# tf1230.net
KiCad netlist of a schematic drawn in EAGLE
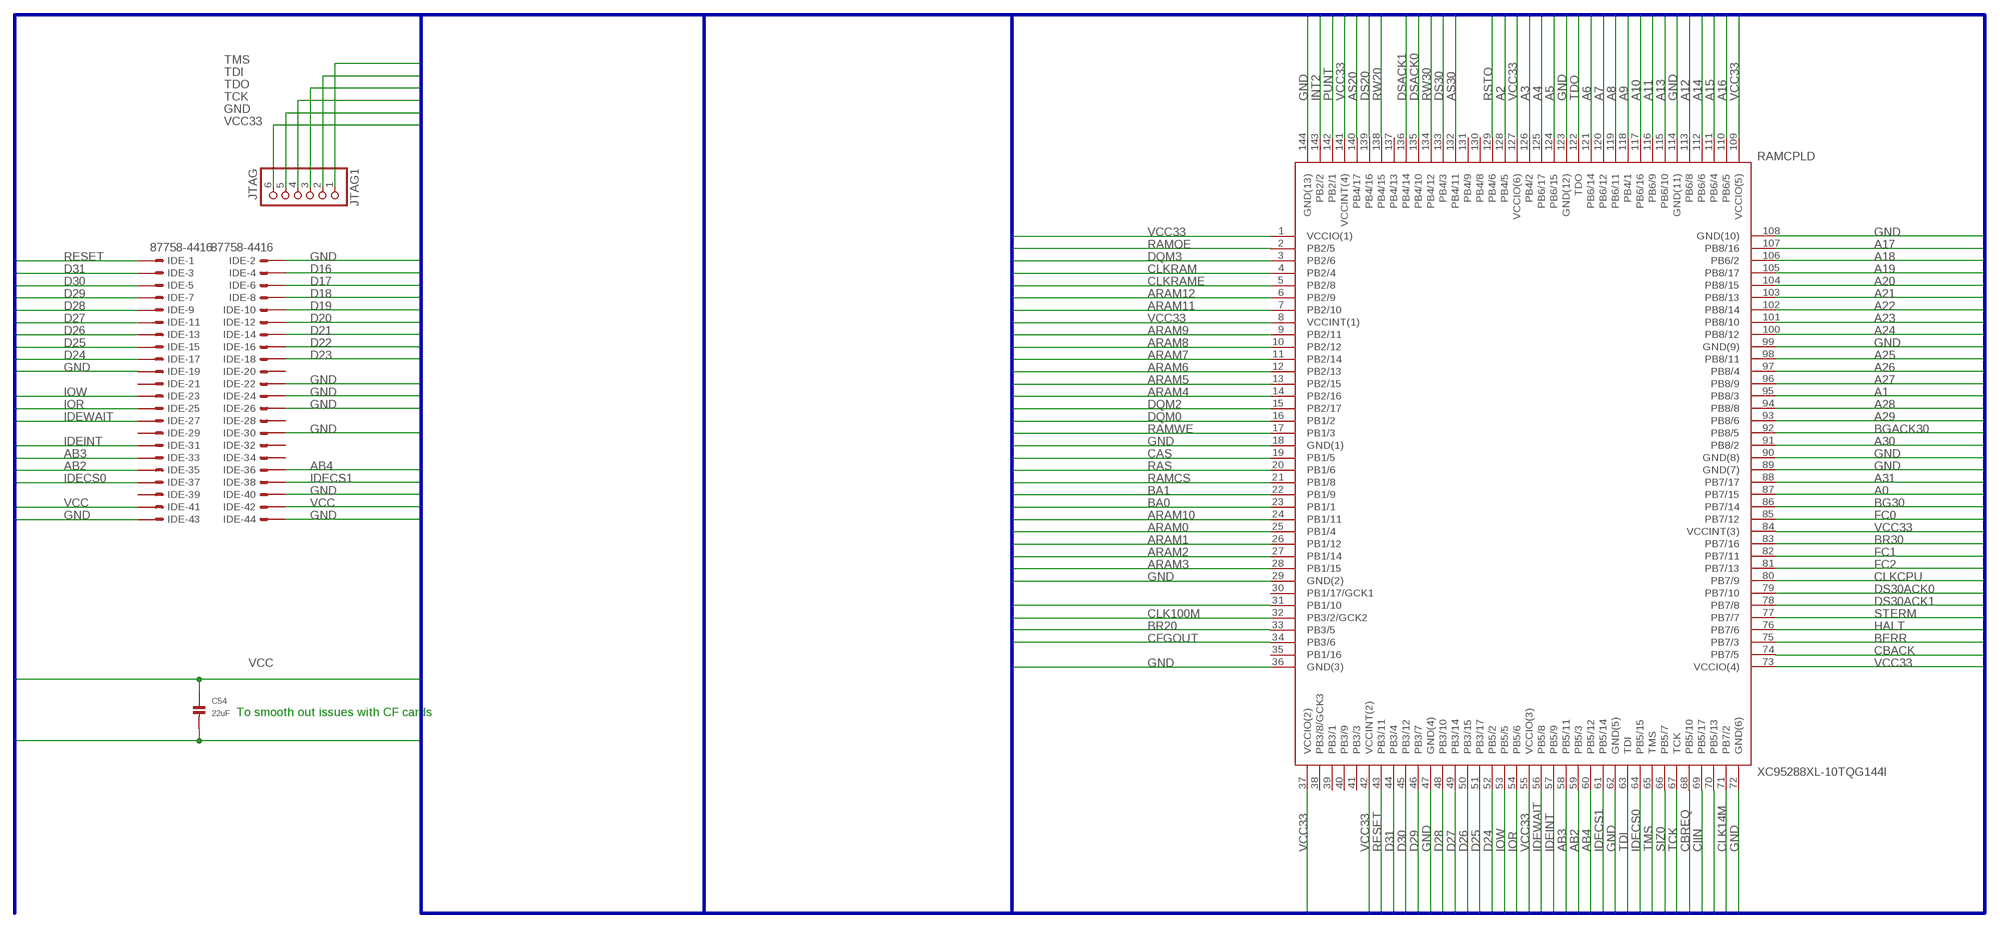
[diagram p0: schematic, sheet 1]
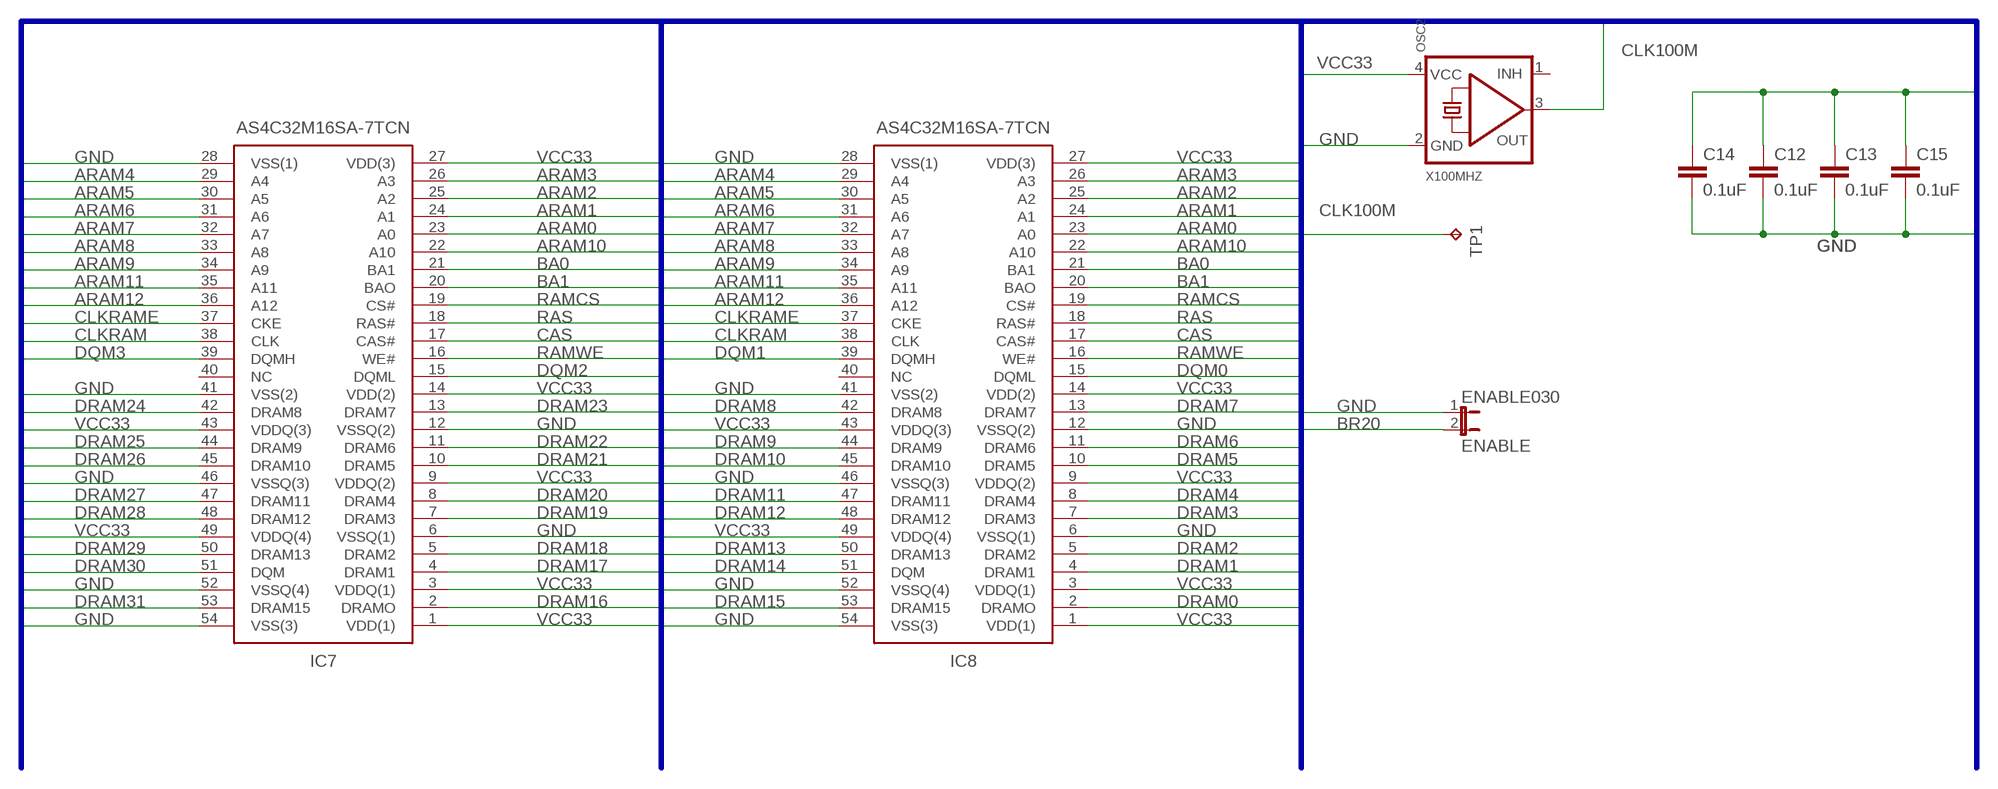
[diagram p1: schematic, sheet 2]
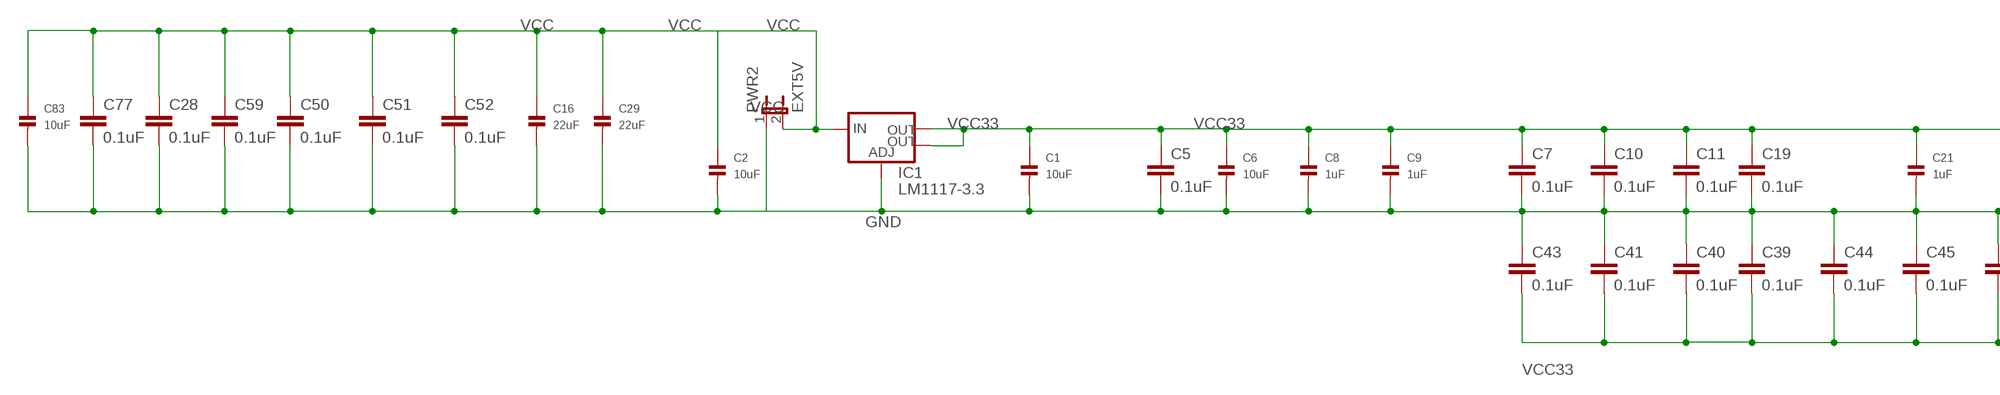
[diagram p2: schematic, sheet 3, part 1 of 2]
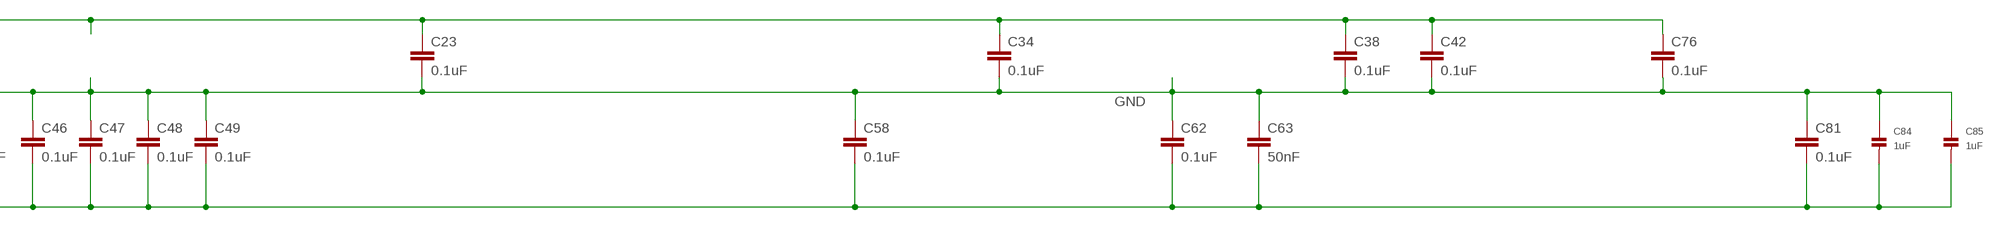
[diagram p3: schematic, sheet 3, part 2 of 2]
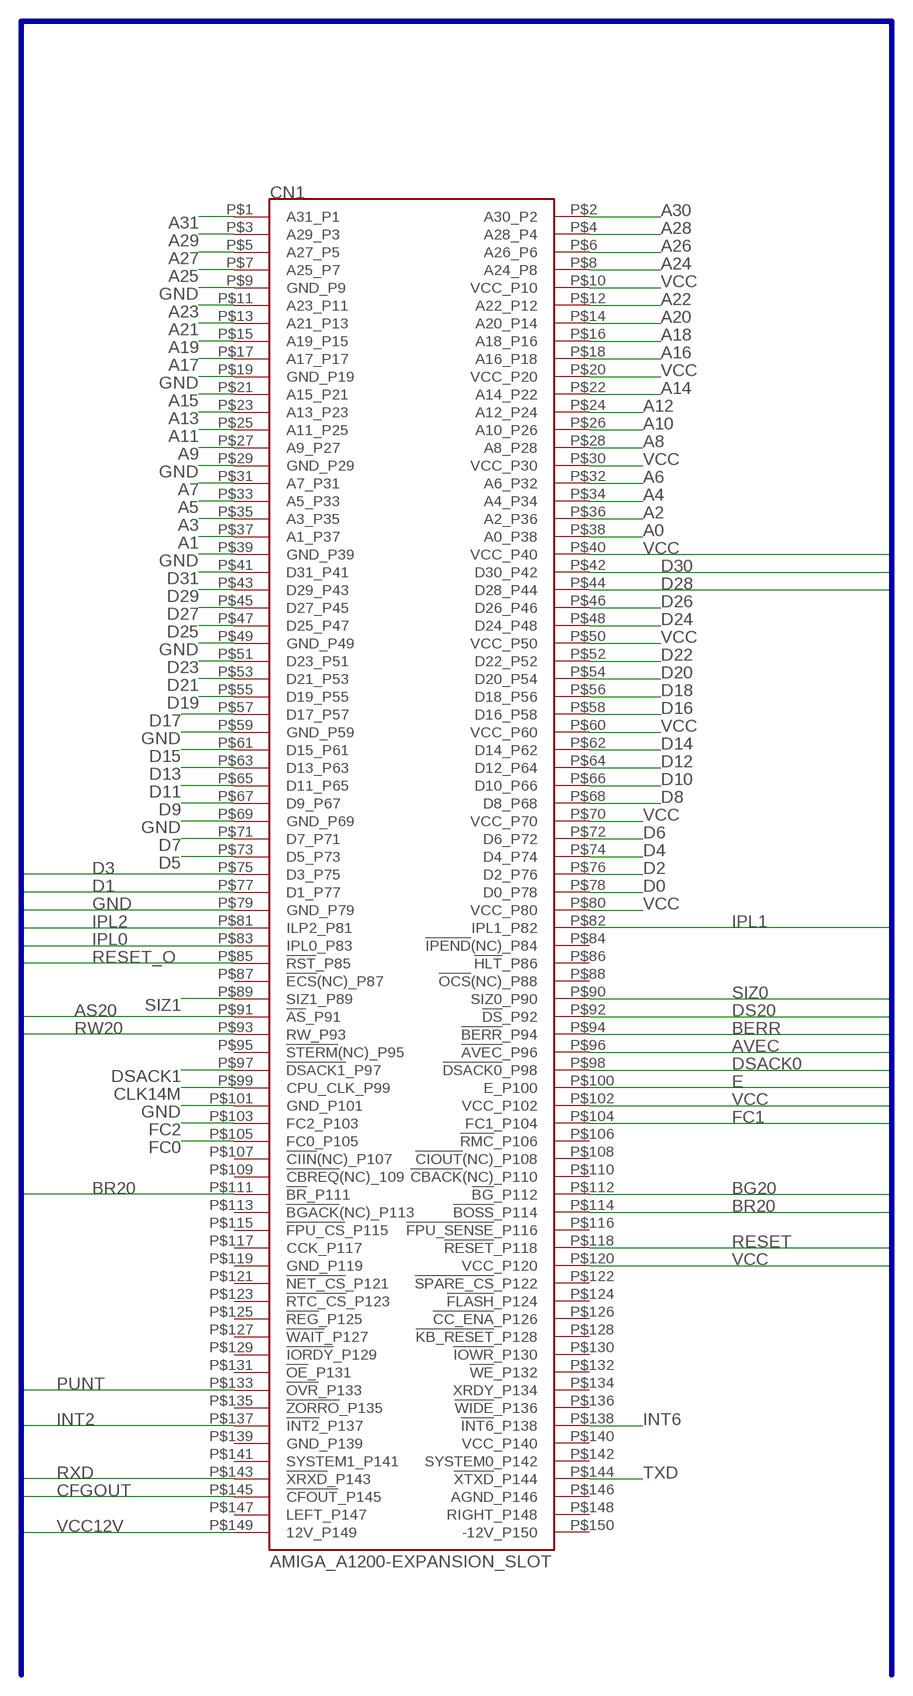
[diagram p4: schematic, sheet 4]
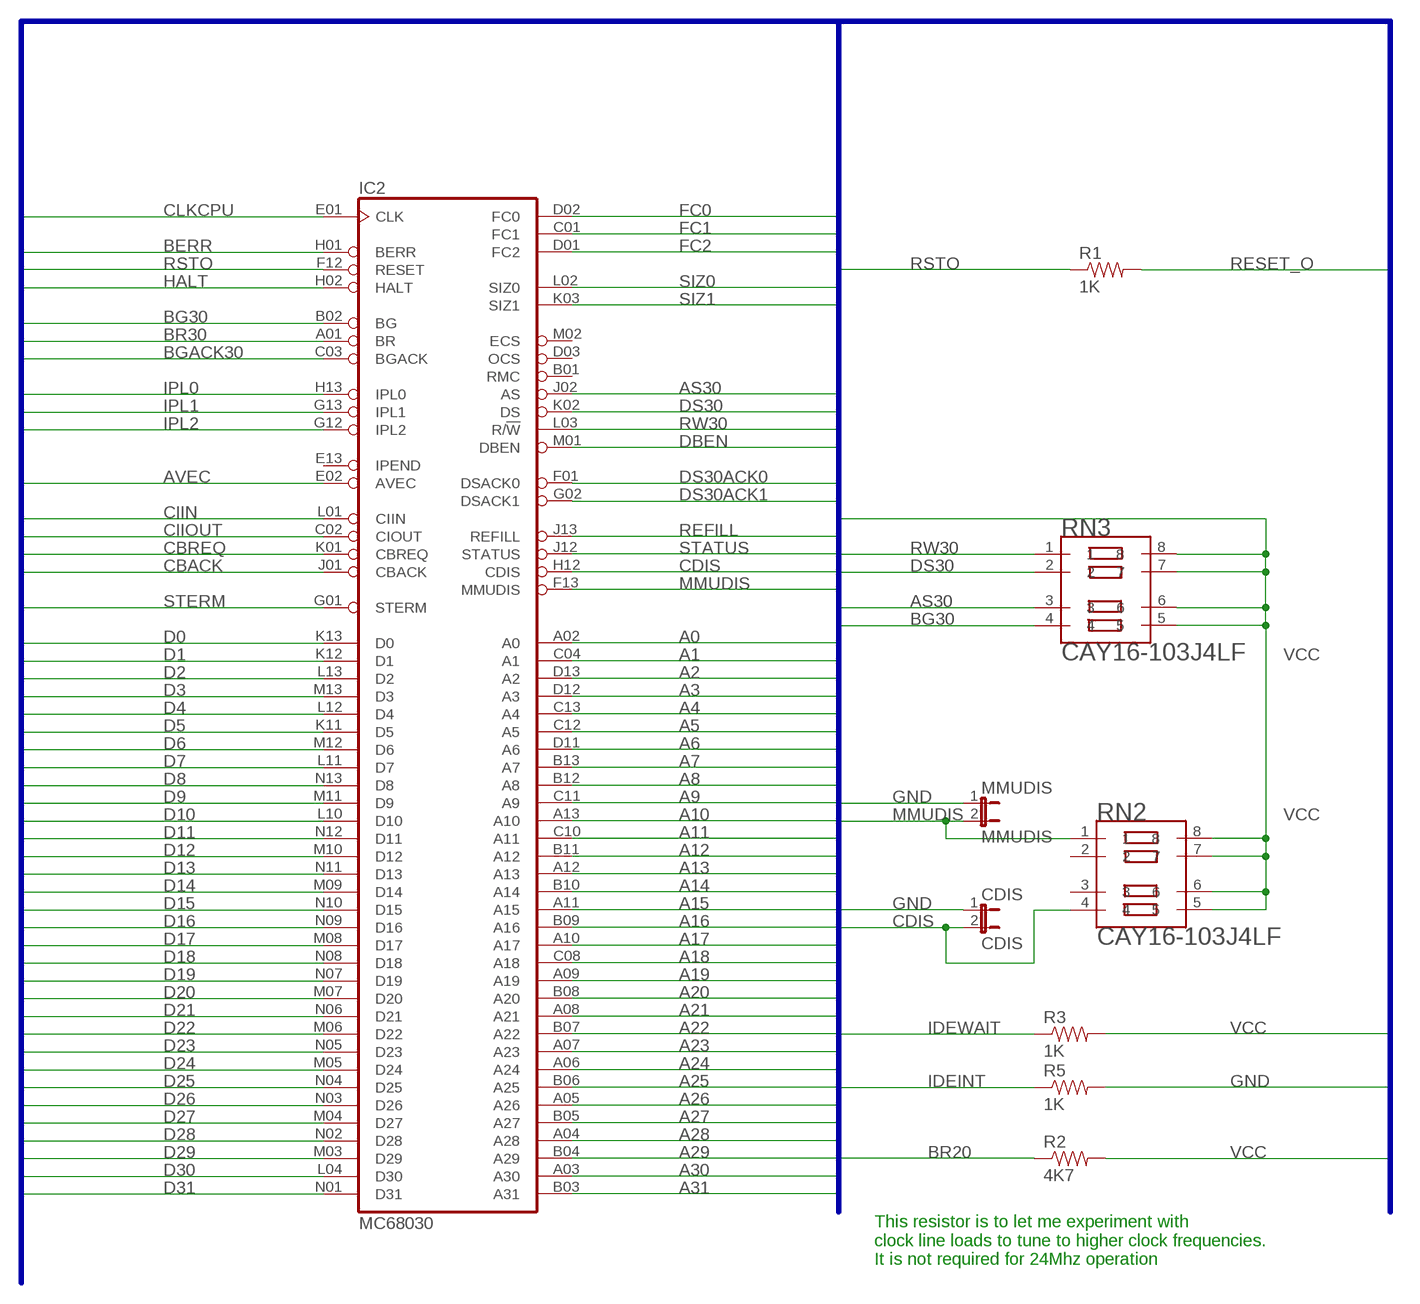
[diagram p5: schematic, sheet 5]
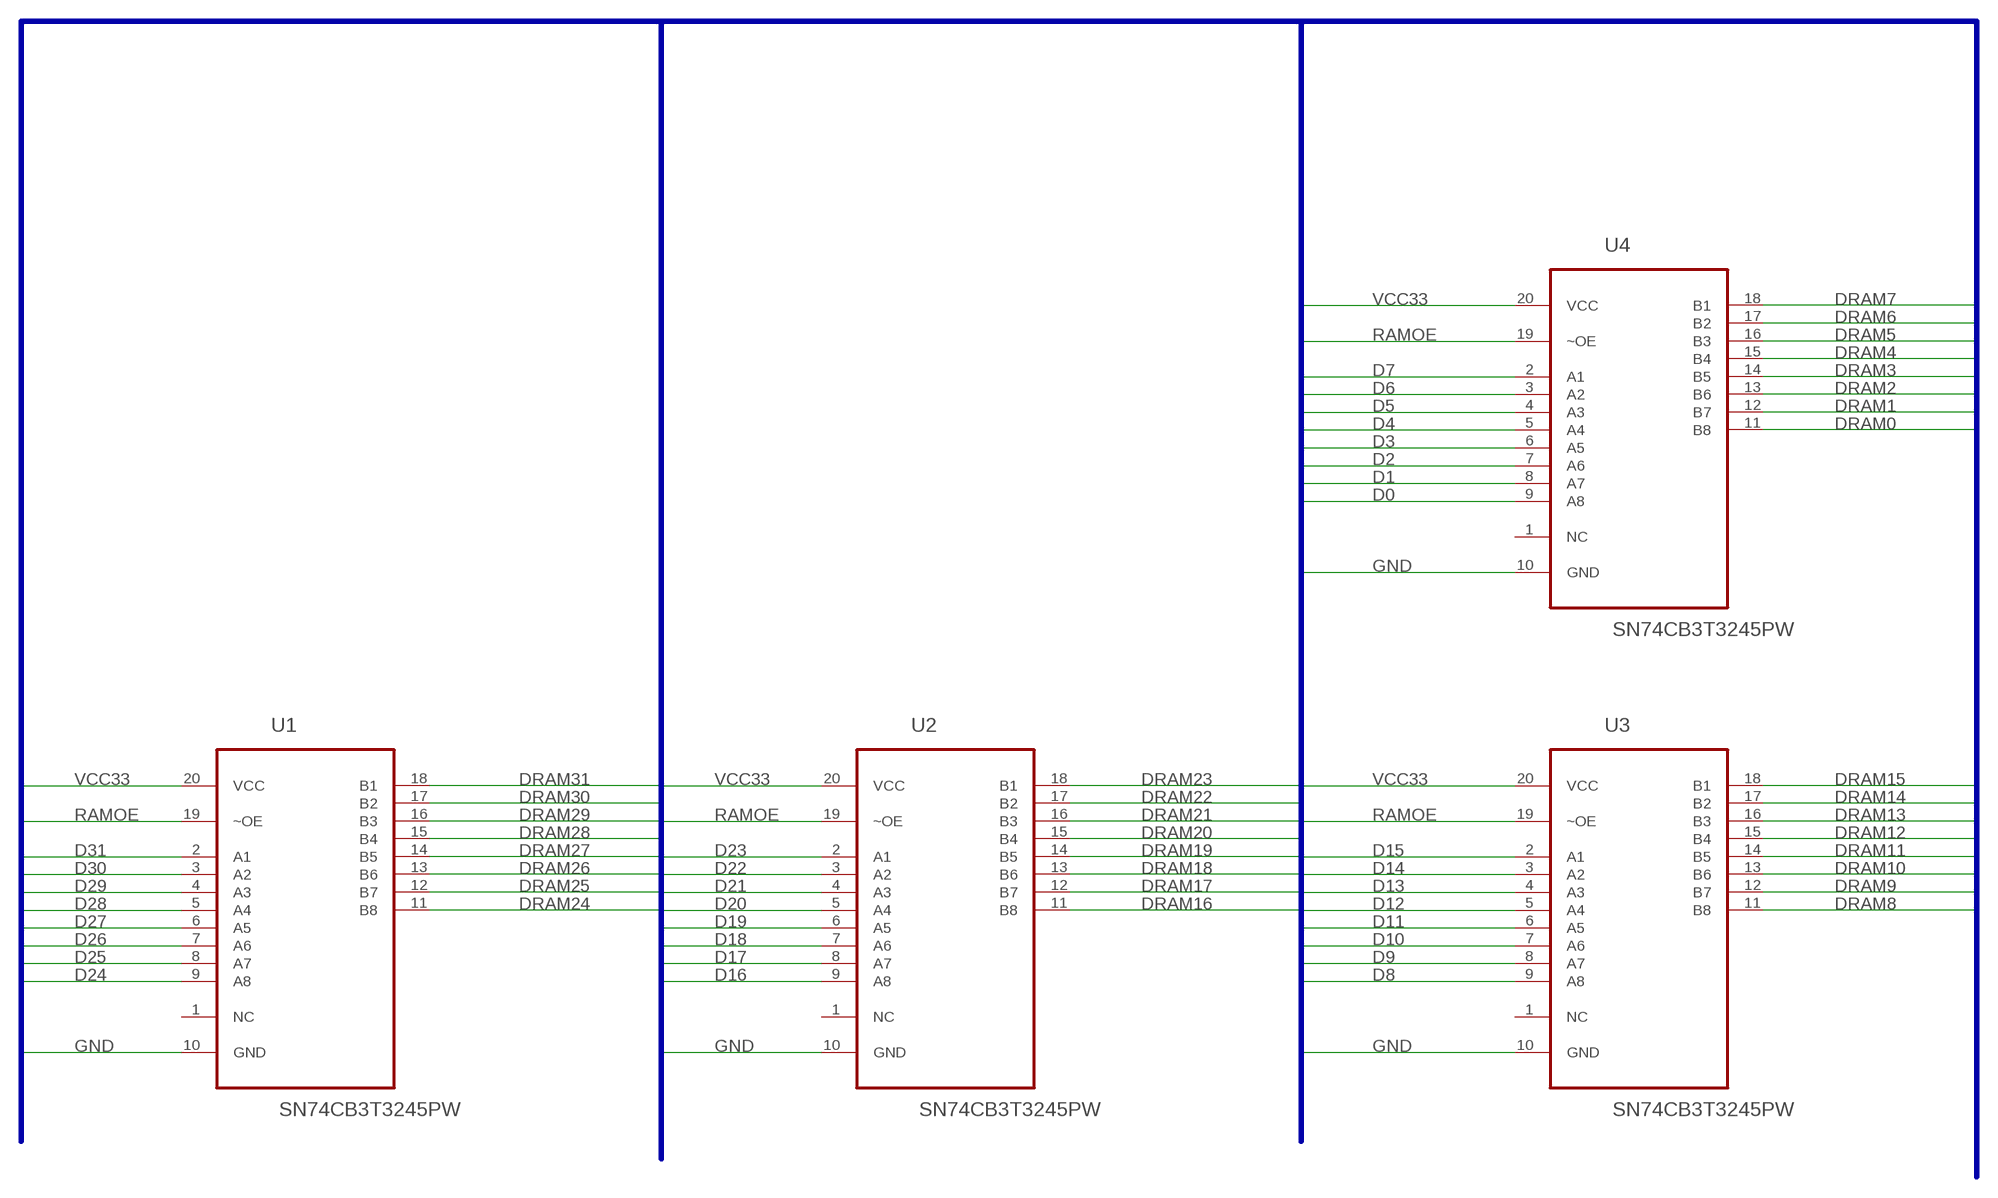
[diagram p6: schematic, sheet 6]

(export (version "E")
  (design (tool "Eeschema 10.0.6"))
  (components
    (comp (ref "CDIS")
      (value "CDIS")
      (footprint "eagle-import:1X02")
      (libsource (lib "eagle-import") (part "JUMPER-2PTH"))
    )
    (comp (ref "IC2")
      (value "MC68030")
      (footprint "eagle-import:MPGA128")
      (fields (field (name "MF") "MOTOROLA") (field (name "MPN") "MC68030RC50C"))
      (libsource (lib "eagle-import") (part "MC68030RC"))
    )
    (comp (ref "MMUDIS")
      (value "MMUDIS")
      (footprint "eagle-import:1X02")
      (libsource (lib "eagle-import") (part "JUMPER-2PTH"))
    )
    (comp (ref "R1")
      (value "1K")
      (footprint "eagle-import:0603")
      (libsource (lib "eagle-import") (part "0.05OHM-1/5W-1%(0603)"))
    )
    (comp (ref "R2")
      (value "4K7")
      (footprint "eagle-import:0603")
      (libsource (lib "eagle-import") (part "0.05OHM-1/5W-1%(0603)"))
    )
    (comp (ref "R3")
      (value "1K")
      (footprint "eagle-import:0603")
      (libsource (lib "eagle-import") (part "0.05OHM-1/5W-1%(0603)"))
    )
    (comp (ref "R5")
      (value "1K")
      (footprint "eagle-import:0603")
      (libsource (lib "eagle-import") (part "0.05OHM-1/5W-1%(0603)"))
    )
    (comp (ref "RN2")
      (value "CAY16-103J4LF")
      (footprint "eagle-import:RESCAXE80P320X160-8N")
      (fields (field (name "MF") "Bourns"))
      (libsource (lib "eagle-import") (part "CAY16-103J4LF"))
    )
    (comp (ref "RN3")
      (value "CAY16-103J4LF")
      (footprint "eagle-import:RESCAXE80P320X160-8N")
      (fields (field (name "MF") "Bourns"))
      (libsource (lib "eagle-import") (part "CAY16-103J4LF"))
    )
    (comp (ref "U1")
      (value "SN74CB3T3245PW")
      (footprint "eagle-import:SOP65P640X120-20N")
      (fields (field (name "MF") "Texas Instruments"))
      (libsource (lib "eagle-import") (part "SN74CB3T3245PW"))
    )
    (comp (ref "U2")
      (value "SN74CB3T3245PW")
      (footprint "eagle-import:SOP65P640X120-20N")
      (fields (field (name "MF") "Texas Instruments"))
      (libsource (lib "eagle-import") (part "SN74CB3T3245PW"))
    )
    (comp (ref "U3")
      (value "SN74CB3T3245PW")
      (footprint "eagle-import:SOP65P640X120-20N")
      (fields (field (name "MF") "Texas Instruments"))
      (libsource (lib "eagle-import") (part "SN74CB3T3245PW"))
    )
    (comp (ref "U4")
      (value "SN74CB3T3245PW")
      (footprint "eagle-import:SOP65P640X120-20N")
      (fields (field (name "MF") "Texas Instruments"))
      (libsource (lib "eagle-import") (part "SN74CB3T3245PW"))
    )
    (comp (ref "C54")
      (value "22uF")
      (footprint "eagle-import:1206")
      (libsource (lib "eagle-import") (part "CAP_CERAMIC1206"))
    )
    (comp (ref "IDE")
      (value "87758-4416")
      (footprint "eagle-import:87758-4416")
      (fields (field (name "MF") "MOLEX"))
      (libsource (lib "eagle-import") (part "87758-4416"))
    )
    (comp (ref "JTAG1")
      (value "JTAG")
      (footprint "eagle-import:1X06_ROUND")
      (libsource (lib "eagle-import") (part "HEADER-1X6ROUND"))
    )
    (comp (ref "RAMCPLD")
      (value "XC95288XL-10TQG144I")
      (footprint "eagle-import:SAMACSYS_PARTS_QFP50P2200X2200X160-144N")
      (fields
        (field (name "MANUFACTURER_PART_NUMBER") "XC95144XL-10TQG144I")
        (field (name "RS_PART_NUMBER") "6260624")
      )
      (libsource (lib "eagle-import") (part "SAMACSYS_PARTS_XC95144XL-10TQG144I"))
    )
    (comp (ref "C12")
      (value "0.1uF")
      (footprint "eagle-import:0603-CAP")
      (libsource (lib "eagle-import") (part "0.1UF-25V(+80/-20%)(0603)"))
    )
    (comp (ref "C13")
      (value "0.1uF")
      (footprint "eagle-import:0603-CAP")
      (libsource (lib "eagle-import") (part "0.1UF-25V(+80/-20%)(0603)"))
    )
    (comp (ref "C14")
      (value "0.1uF")
      (footprint "eagle-import:0603-CAP")
      (libsource (lib "eagle-import") (part "0.1UF-25V(+80/-20%)(0603)"))
    )
    (comp (ref "C15")
      (value "0.1uF")
      (footprint "eagle-import:0603-CAP")
      (libsource (lib "eagle-import") (part "0.1UF-25V(+80/-20%)(0603)"))
    )
    (comp (ref "ENABLE030")
      (value "ENABLE")
      (footprint "eagle-import:1X02")
      (libsource (lib "eagle-import") (part "JUMPER-2PTH"))
    )
    (comp (ref "IC7")
      (value "AS4C32M16SA-7TCN")
      (footprint "eagle-import:SOP80P1176X120-54N")
      (fields
        (field (name "MANUFACTURER_PART_NUMBER") "MT48LC16M16A2P-6A:G")
        (field (name "RS_PART_NUMBER") "7824553")
      )
      (libsource (lib "eagle-import") (part "MT48LC16M16A2P-6A_G"))
    )
    (comp (ref "IC8")
      (value "AS4C32M16SA-7TCN")
      (footprint "eagle-import:SOP80P1176X120-54N")
      (fields
        (field (name "MANUFACTURER_PART_NUMBER") "MT48LC16M16A2P-6A:G")
        (field (name "RS_PART_NUMBER") "7824553")
      )
      (libsource (lib "eagle-import") (part "MT48LC16M16A2P-6A_G"))
    )
    (comp (ref "OSC2")
      (value "X100MHZ")
      (footprint "eagle-import:OSC_7X5MM")
      (libsource (lib "eagle-import") (part "OSCILLATOR"))
    )
    (comp (ref "TP1")
      (value "TPB1,27")
      (footprint "eagle-import:B1,27")
      (libsource (lib "eagle-import") (part "TPB1,27"))
    )
    (comp (ref "CN1")
      (value "AMIGA_A1200-EXPANSION_SLOT")
      (footprint "eagle-import:AMIGA_CON_150")
      (libsource (lib "eagle-import") (part "AMIGA_A1200-EXPANSION_SLOT"))
    )
    (comp (ref "C1")
      (value "10uF")
      (footprint "eagle-import:1206")
      (libsource (lib "eagle-import") (part "CAP_CERAMIC1206"))
    )
    (comp (ref "C2")
      (value "10uF")
      (footprint "eagle-import:1206")
      (libsource (lib "eagle-import") (part "CAP_CERAMIC1206"))
    )
    (comp (ref "C5")
      (value "0.1uF")
      (footprint "eagle-import:0603-CAP")
      (libsource (lib "eagle-import") (part "0.1UF-25V(+80/-20%)(0603)"))
    )
    (comp (ref "C6")
      (value "10uF")
      (footprint "eagle-import:1206")
      (libsource (lib "eagle-import") (part "CAP_CERAMIC1206"))
    )
    (comp (ref "C7")
      (value "0.1uF")
      (footprint "eagle-import:0603-CAP")
      (libsource (lib "eagle-import") (part "0.1UF-25V(+80/-20%)(0603)"))
    )
    (comp (ref "C8")
      (value "1uF")
      (footprint "eagle-import:1206")
      (libsource (lib "eagle-import") (part "CAP_CERAMIC1206"))
    )
    (comp (ref "C9")
      (value "1uF")
      (footprint "eagle-import:1206")
      (libsource (lib "eagle-import") (part "CAP_CERAMIC1206"))
    )
    (comp (ref "C10")
      (value "0.1uF")
      (footprint "eagle-import:0603-CAP")
      (libsource (lib "eagle-import") (part "0.1UF-25V(+80/-20%)(0603)"))
    )
    (comp (ref "C11")
      (value "0.1uF")
      (footprint "eagle-import:0603-CAP")
      (libsource (lib "eagle-import") (part "0.1UF-25V(+80/-20%)(0603)"))
    )
    (comp (ref "C16")
      (value "22uF")
      (footprint "eagle-import:1206")
      (libsource (lib "eagle-import") (part "CAP_CERAMIC1206"))
    )
    (comp (ref "C19")
      (value "0.1uF")
      (footprint "eagle-import:0603-CAP")
      (libsource (lib "eagle-import") (part "0.1UF-25V(+80/-20%)(0603)"))
    )
    (comp (ref "C21")
      (value "1uF")
      (footprint "eagle-import:1206")
      (libsource (lib "eagle-import") (part "CAP_CERAMIC1206"))
    )
    (comp (ref "C23")
      (value "0.1uF")
      (footprint "eagle-import:0603-CAP")
      (libsource (lib "eagle-import") (part "0.1UF-25V(+80/-20%)(0603)"))
    )
    (comp (ref "C28")
      (value "0.1uF")
      (footprint "eagle-import:0603-CAP")
      (libsource (lib "eagle-import") (part "0.1UF-25V(+80/-20%)(0603)"))
    )
    (comp (ref "C29")
      (value "22uF")
      (footprint "eagle-import:1206")
      (libsource (lib "eagle-import") (part "CAP_CERAMIC1206"))
    )
    (comp (ref "C34")
      (value "0.1uF")
      (footprint "eagle-import:0603-CAP")
      (libsource (lib "eagle-import") (part "0.1UF-25V(+80/-20%)(0603)"))
    )
    (comp (ref "C38")
      (value "0.1uF")
      (footprint "eagle-import:0603-CAP")
      (libsource (lib "eagle-import") (part "0.1UF-25V(+80/-20%)(0603)"))
    )
    (comp (ref "C39")
      (value "0.1uF")
      (footprint "eagle-import:0603-CAP")
      (libsource (lib "eagle-import") (part "0.1UF-25V(+80/-20%)(0603)"))
    )
    (comp (ref "C40")
      (value "0.1uF")
      (footprint "eagle-import:0603-CAP")
      (libsource (lib "eagle-import") (part "0.1UF-25V(+80/-20%)(0603)"))
    )
    (comp (ref "C41")
      (value "0.1uF")
      (footprint "eagle-import:0603-CAP")
      (libsource (lib "eagle-import") (part "0.1UF-25V(+80/-20%)(0603)"))
    )
    (comp (ref "C42")
      (value "0.1uF")
      (footprint "eagle-import:0603-CAP")
      (libsource (lib "eagle-import") (part "0.1UF-25V(+80/-20%)(0603)"))
    )
    (comp (ref "C43")
      (value "0.1uF")
      (footprint "eagle-import:0603-CAP")
      (libsource (lib "eagle-import") (part "0.1UF-25V(+80/-20%)(0603)"))
    )
    (comp (ref "C44")
      (value "0.1uF")
      (footprint "eagle-import:0603-CAP")
      (libsource (lib "eagle-import") (part "0.1UF-25V(+80/-20%)(0603)"))
    )
    (comp (ref "C45")
      (value "0.1uF")
      (footprint "eagle-import:0603-CAP")
      (libsource (lib "eagle-import") (part "0.1UF-25V(+80/-20%)(0603)"))
    )
    (comp (ref "C46")
      (value "0.1uF")
      (footprint "eagle-import:0603-CAP")
      (libsource (lib "eagle-import") (part "0.1UF-25V(+80/-20%)(0603)"))
    )
    (comp (ref "C47")
      (value "0.1uF")
      (footprint "eagle-import:0603-CAP")
      (libsource (lib "eagle-import") (part "0.1UF-25V(+80/-20%)(0603)"))
    )
    (comp (ref "C48")
      (value "0.1uF")
      (footprint "eagle-import:0603-CAP")
      (libsource (lib "eagle-import") (part "0.1UF-25V(+80/-20%)(0603)"))
    )
    (comp (ref "C49")
      (value "0.1uF")
      (footprint "eagle-import:0603-CAP")
      (libsource (lib "eagle-import") (part "0.1UF-25V(+80/-20%)(0603)"))
    )
    (comp (ref "C50")
      (value "0.1uF")
      (footprint "eagle-import:0603-CAP")
      (libsource (lib "eagle-import") (part "0.1UF-25V(+80/-20%)(0603)"))
    )
    (comp (ref "C51")
      (value "0.1uF")
      (footprint "eagle-import:0603-CAP")
      (libsource (lib "eagle-import") (part "0.1UF-25V(+80/-20%)(0603)"))
    )
    (comp (ref "C52")
      (value "0.1uF")
      (footprint "eagle-import:0603-CAP")
      (libsource (lib "eagle-import") (part "0.1UF-25V(+80/-20%)(0603)"))
    )
    (comp (ref "C58")
      (value "0.1uF")
      (footprint "eagle-import:0603-CAP")
      (libsource (lib "eagle-import") (part "0.1UF-25V(+80/-20%)(0603)"))
    )
    (comp (ref "C59")
      (value "0.1uF")
      (footprint "eagle-import:0603-CAP")
      (libsource (lib "eagle-import") (part "0.1UF-25V(+80/-20%)(0603)"))
    )
    (comp (ref "C62")
      (value "0.1uF")
      (footprint "eagle-import:0603-CAP")
      (libsource (lib "eagle-import") (part "0.1UF-25V(+80/-20%)(0603)"))
    )
    (comp (ref "C63")
      (value "50nF")
      (footprint "eagle-import:0603-CAP")
      (libsource (lib "eagle-import") (part "0.1UF-25V(+80/-20%)(0603)"))
    )
    (comp (ref "C76")
      (value "0.1uF")
      (footprint "eagle-import:0603-CAP")
      (libsource (lib "eagle-import") (part "0.1UF-25V(+80/-20%)(0603)"))
    )
    (comp (ref "C77")
      (value "0.1uF")
      (footprint "eagle-import:0603-CAP")
      (libsource (lib "eagle-import") (part "0.1UF-25V(+80/-20%)(0603)"))
    )
    (comp (ref "C81")
      (value "0.1uF")
      (footprint "eagle-import:0603-CAP")
      (libsource (lib "eagle-import") (part "0.1UF-25V(+80/-20%)(0603)"))
    )
    (comp (ref "C83")
      (value "10uF")
      (footprint "eagle-import:1206")
      (libsource (lib "eagle-import") (part "CAP_CERAMIC1206"))
    )
    (comp (ref "C84")
      (value "1uF")
      (footprint "eagle-import:1206")
      (libsource (lib "eagle-import") (part "CAP_CERAMIC1206"))
    )
    (comp (ref "C85")
      (value "1uF")
      (footprint "eagle-import:1206")
      (libsource (lib "eagle-import") (part "CAP_CERAMIC1206"))
    )
    (comp (ref "IC1")
      (value "LM1117-3.3")
      (footprint "eagle-import:SOT223")
      (libsource (lib "eagle-import") (part "V_REG_LM1117SOT223"))
    )
    (comp (ref "PWR2")
      (value "EXT5V")
      (footprint "eagle-import:1X02")
      (libsource (lib "eagle-import") (part "JUMPER-2PTH"))
    )
  )
  (nets
    (net (code "1") (name "A0") (class "Default")
      (node (ref "CN1") (pin "P$38") (pinfunction "A0_P38_P$38") (pintype "bidirectional"))
      (node (ref "IC2") (pin "A02") (pinfunction "A0_A02") (pintype "output"))
      (node (ref "RAMCPLD") (pin "87") (pinfunction "PB7/15_87") (pintype "input"))
    )
    (net (code "2") (name "A1") (class "Default")
      (node (ref "CN1") (pin "P$37") (pinfunction "A1_P37_P$37") (pintype "bidirectional"))
      (node (ref "IC2") (pin "C04") (pinfunction "A1_C04") (pintype "output"))
      (node (ref "RAMCPLD") (pin "95") (pinfunction "PB8/3_95") (pintype "input"))
    )
    (net (code "3") (name "A2") (class "Default")
      (node (ref "CN1") (pin "P$36") (pinfunction "A2_P36_P$36") (pintype "bidirectional"))
      (node (ref "IC2") (pin "D13") (pinfunction "A2_D13") (pintype "output"))
      (node (ref "RAMCPLD") (pin "128") (pinfunction "PB4/5_128") (pintype "input"))
    )
    (net (code "4") (name "A3") (class "Default")
      (node (ref "CN1") (pin "P$35") (pinfunction "A3_P35_P$35") (pintype "bidirectional"))
      (node (ref "IC2") (pin "D12") (pinfunction "A3_D12") (pintype "output"))
      (node (ref "RAMCPLD") (pin "126") (pinfunction "PB4/2_126") (pintype "input"))
    )
    (net (code "5") (name "A4") (class "Default")
      (node (ref "CN1") (pin "P$34") (pinfunction "A4_P34_P$34") (pintype "bidirectional"))
      (node (ref "IC2") (pin "C13") (pinfunction "A4_C13") (pintype "output"))
      (node (ref "RAMCPLD") (pin "125") (pinfunction "PB6/17_125") (pintype "input"))
    )
    (net (code "6") (name "A5") (class "Default")
      (node (ref "CN1") (pin "P$33") (pinfunction "A5_P33_P$33") (pintype "bidirectional"))
      (node (ref "IC2") (pin "C12") (pinfunction "A5_C12") (pintype "output"))
      (node (ref "RAMCPLD") (pin "124") (pinfunction "PB6/15_124") (pintype "input"))
    )
    (net (code "7") (name "A6") (class "Default")
      (node (ref "CN1") (pin "P$32") (pinfunction "A6_P32_P$32") (pintype "bidirectional"))
      (node (ref "IC2") (pin "D11") (pinfunction "A6_D11") (pintype "output"))
      (node (ref "RAMCPLD") (pin "121") (pinfunction "PB6/14_121") (pintype "input"))
    )
    (net (code "8") (name "A7") (class "Default")
      (node (ref "CN1") (pin "P$31") (pinfunction "A7_P31_P$31") (pintype "bidirectional"))
      (node (ref "IC2") (pin "B13") (pinfunction "A7_B13") (pintype "output"))
      (node (ref "RAMCPLD") (pin "120") (pinfunction "PB6/12_120") (pintype "input"))
    )
    (net (code "9") (name "A8") (class "Default")
      (node (ref "CN1") (pin "P$28") (pinfunction "A8_P28_P$28") (pintype "bidirectional"))
      (node (ref "IC2") (pin "B12") (pinfunction "A8_B12") (pintype "output"))
      (node (ref "RAMCPLD") (pin "119") (pinfunction "PB6/11_119") (pintype "input"))
    )
    (net (code "10") (name "A9") (class "Default")
      (node (ref "CN1") (pin "P$27") (pinfunction "A9_P27_P$27") (pintype "bidirectional"))
      (node (ref "IC2") (pin "C11") (pinfunction "A9_C11") (pintype "output"))
      (node (ref "RAMCPLD") (pin "118") (pinfunction "PB4/1_118") (pintype "input"))
    )
    (net (code "11") (name "A10") (class "Default")
      (node (ref "CN1") (pin "P$26") (pinfunction "A10_P26_P$26") (pintype "bidirectional"))
      (node (ref "IC2") (pin "A13") (pinfunction "A10_A13") (pintype "output"))
      (node (ref "RAMCPLD") (pin "117") (pinfunction "PB6/16_117") (pintype "input"))
    )
    (net (code "12") (name "A11") (class "Default")
      (node (ref "CN1") (pin "P$25") (pinfunction "A11_P25_P$25") (pintype "bidirectional"))
      (node (ref "IC2") (pin "C10") (pinfunction "A11_C10") (pintype "output"))
      (node (ref "RAMCPLD") (pin "116") (pinfunction "PB6/9_116") (pintype "input"))
    )
    (net (code "13") (name "A12") (class "Default")
      (node (ref "CN1") (pin "P$24") (pinfunction "A12_P24_P$24") (pintype "bidirectional"))
      (node (ref "IC2") (pin "B11") (pinfunction "A12_B11") (pintype "output"))
      (node (ref "RAMCPLD") (pin "113") (pinfunction "PB6/8_113") (pintype "input"))
    )
    (net (code "14") (name "A13") (class "Default")
      (node (ref "CN1") (pin "P$23") (pinfunction "A13_P23_P$23") (pintype "bidirectional"))
      (node (ref "IC2") (pin "A12") (pinfunction "A13_A12") (pintype "output"))
      (node (ref "RAMCPLD") (pin "115") (pinfunction "PB6/10_115") (pintype "input"))
    )
    (net (code "15") (name "A14") (class "Default")
      (node (ref "CN1") (pin "P$22") (pinfunction "A14_P22_P$22") (pintype "bidirectional"))
      (node (ref "IC2") (pin "B10") (pinfunction "A14_B10") (pintype "output"))
      (node (ref "RAMCPLD") (pin "112") (pinfunction "PB6/6_112") (pintype "input"))
    )
    (net (code "16") (name "A15") (class "Default")
      (node (ref "CN1") (pin "P$21") (pinfunction "A15_P21_P$21") (pintype "bidirectional"))
      (node (ref "IC2") (pin "A11") (pinfunction "A15_A11") (pintype "output"))
      (node (ref "RAMCPLD") (pin "111") (pinfunction "PB6/4_111") (pintype "input"))
    )
    (net (code "17") (name "A16") (class "Default")
      (node (ref "CN1") (pin "P$18") (pinfunction "A16_P18_P$18") (pintype "bidirectional"))
      (node (ref "IC2") (pin "B09") (pinfunction "A16_B09") (pintype "output"))
      (node (ref "RAMCPLD") (pin "110") (pinfunction "PB6/5_110") (pintype "input"))
    )
    (net (code "18") (name "A17") (class "Default")
      (node (ref "CN1") (pin "P$17") (pinfunction "A17_P17_P$17") (pintype "bidirectional"))
      (node (ref "IC2") (pin "A10") (pinfunction "A17_A10") (pintype "output"))
      (node (ref "RAMCPLD") (pin "107") (pinfunction "PB8/16_107") (pintype "input"))
    )
    (net (code "19") (name "A18") (class "Default")
      (node (ref "CN1") (pin "P$16") (pinfunction "A18_P16_P$16") (pintype "bidirectional"))
      (node (ref "IC2") (pin "C08") (pinfunction "A18_C08") (pintype "output"))
      (node (ref "RAMCPLD") (pin "106") (pinfunction "PB6/2_106") (pintype "input"))
    )
    (net (code "20") (name "A19") (class "Default")
      (node (ref "CN1") (pin "P$15") (pinfunction "A19_P15_P$15") (pintype "bidirectional"))
      (node (ref "IC2") (pin "A09") (pinfunction "A19_A09") (pintype "output"))
      (node (ref "RAMCPLD") (pin "105") (pinfunction "PB8/17_105") (pintype "input"))
    )
    (net (code "21") (name "A20") (class "Default")
      (node (ref "CN1") (pin "P$14") (pinfunction "A20_P14_P$14") (pintype "bidirectional"))
      (node (ref "IC2") (pin "B08") (pinfunction "A20_B08") (pintype "output"))
      (node (ref "RAMCPLD") (pin "104") (pinfunction "PB8/15_104") (pintype "input"))
    )
    (net (code "22") (name "A21") (class "Default")
      (node (ref "CN1") (pin "P$13") (pinfunction "A21_P13_P$13") (pintype "bidirectional"))
      (node (ref "IC2") (pin "A08") (pinfunction "A21_A08") (pintype "output"))
      (node (ref "RAMCPLD") (pin "103") (pinfunction "PB8/13_103") (pintype "input"))
    )
    (net (code "23") (name "A22") (class "Default")
      (node (ref "CN1") (pin "P$12") (pinfunction "A22_P12_P$12") (pintype "bidirectional"))
      (node (ref "IC2") (pin "B07") (pinfunction "A22_B07") (pintype "output"))
      (node (ref "RAMCPLD") (pin "102") (pinfunction "PB8/14_102") (pintype "input"))
    )
    (net (code "24") (name "A23") (class "Default")
      (node (ref "CN1") (pin "P$11") (pinfunction "A23_P11_P$11") (pintype "bidirectional"))
      (node (ref "IC2") (pin "A07") (pinfunction "A23_A07") (pintype "output"))
      (node (ref "RAMCPLD") (pin "101") (pinfunction "PB8/10_101") (pintype "input"))
    )
    (net (code "25") (name "A24") (class "Default")
      (node (ref "CN1") (pin "P$8") (pinfunction "A24_P8_P$8") (pintype "bidirectional"))
      (node (ref "IC2") (pin "A06") (pinfunction "A24_A06") (pintype "output"))
      (node (ref "RAMCPLD") (pin "100") (pinfunction "PB8/12_100") (pintype "input"))
    )
    (net (code "26") (name "A25") (class "Default")
      (node (ref "CN1") (pin "P$7") (pinfunction "A25_P7_P$7") (pintype "bidirectional"))
      (node (ref "IC2") (pin "B06") (pinfunction "A25_B06") (pintype "output"))
      (node (ref "RAMCPLD") (pin "98") (pinfunction "PB8/11_98") (pintype "input"))
    )
    (net (code "27") (name "A26") (class "Default")
      (node (ref "CN1") (pin "P$6") (pinfunction "A26_P6_P$6") (pintype "bidirectional"))
      (node (ref "IC2") (pin "A05") (pinfunction "A26_A05") (pintype "output"))
      (node (ref "RAMCPLD") (pin "97") (pinfunction "PB8/4_97") (pintype "input"))
    )
    (net (code "28") (name "A27") (class "Default")
      (node (ref "CN1") (pin "P$5") (pinfunction "A27_P5_P$5") (pintype "bidirectional"))
      (node (ref "IC2") (pin "B05") (pinfunction "A27_B05") (pintype "output"))
      (node (ref "RAMCPLD") (pin "96") (pinfunction "PB8/9_96") (pintype "input"))
    )
    (net (code "29") (name "A28") (class "Default")
      (node (ref "CN1") (pin "P$4") (pinfunction "A28_P4_P$4") (pintype "bidirectional"))
      (node (ref "IC2") (pin "A04") (pinfunction "A28_A04") (pintype "output"))
      (node (ref "RAMCPLD") (pin "94") (pinfunction "PB8/8_94") (pintype "input"))
    )
    (net (code "30") (name "A29") (class "Default")
      (node (ref "CN1") (pin "P$3") (pinfunction "A29_P3_P$3") (pintype "bidirectional"))
      (node (ref "IC2") (pin "B04") (pinfunction "A29_B04") (pintype "output"))
      (node (ref "RAMCPLD") (pin "93") (pinfunction "PB8/6_93") (pintype "input"))
    )
    (net (code "31") (name "A30") (class "Default")
      (node (ref "CN1") (pin "P$2") (pinfunction "A30_P2_P$2") (pintype "bidirectional"))
      (node (ref "IC2") (pin "A03") (pinfunction "A30_A03") (pintype "output"))
      (node (ref "RAMCPLD") (pin "91") (pinfunction "PB8/2_91") (pintype "input"))
    )
    (net (code "32") (name "A31") (class "Default")
      (node (ref "CN1") (pin "P$1") (pinfunction "A31_P1_P$1") (pintype "bidirectional"))
      (node (ref "IC2") (pin "B03") (pinfunction "A31_B03") (pintype "output"))
      (node (ref "RAMCPLD") (pin "88") (pinfunction "PB7/17_88") (pintype "input"))
    )
    (net (code "33") (name "AB2") (class "Default")
      (node (ref "IDE") (pin "35") (pinfunction "S_35") (pintype "passive"))
      (node (ref "RAMCPLD") (pin "59") (pinfunction "PB5/3_59") (pintype "input"))
    )
    (net (code "34") (name "AB3") (class "Default")
      (node (ref "IDE") (pin "33") (pinfunction "S_33") (pintype "passive"))
      (node (ref "RAMCPLD") (pin "58") (pinfunction "PB5/11_58") (pintype "input"))
    )
    (net (code "35") (name "AB4") (class "Default")
      (node (ref "IDE") (pin "36") (pinfunction "S_36") (pintype "passive"))
      (node (ref "RAMCPLD") (pin "60") (pinfunction "PB5/12_60") (pintype "input"))
    )
    (net (code "36") (name "ARAM0") (class "Default")
      (node (ref "IC7") (pin "23") (pinfunction "A0_23") (pintype "input"))
      (node (ref "IC8") (pin "23") (pinfunction "A0_23") (pintype "input"))
      (node (ref "RAMCPLD") (pin "25") (pinfunction "PB1/4_25") (pintype "input"))
    )
    (net (code "37") (name "ARAM1") (class "Default")
      (node (ref "IC7") (pin "24") (pinfunction "A1_24") (pintype "input"))
      (node (ref "IC8") (pin "24") (pinfunction "A1_24") (pintype "input"))
      (node (ref "RAMCPLD") (pin "26") (pinfunction "PB1/12_26") (pintype "input"))
    )
    (net (code "38") (name "ARAM2") (class "Default")
      (node (ref "IC7") (pin "25") (pinfunction "A2_25") (pintype "input"))
      (node (ref "IC8") (pin "25") (pinfunction "A2_25") (pintype "input"))
      (node (ref "RAMCPLD") (pin "27") (pinfunction "PB1/14_27") (pintype "input"))
    )
    (net (code "39") (name "ARAM3") (class "Default")
      (node (ref "IC7") (pin "26") (pinfunction "A3_26") (pintype "input"))
      (node (ref "IC8") (pin "26") (pinfunction "A3_26") (pintype "input"))
      (node (ref "RAMCPLD") (pin "28") (pinfunction "PB1/15_28") (pintype "input"))
    )
    (net (code "40") (name "ARAM4") (class "Default")
      (node (ref "IC7") (pin "29") (pinfunction "A4_29") (pintype "input"))
      (node (ref "IC8") (pin "29") (pinfunction "A4_29") (pintype "input"))
      (node (ref "RAMCPLD") (pin "14") (pinfunction "PB2/16_14") (pintype "input"))
    )
    (net (code "41") (name "ARAM5") (class "Default")
      (node (ref "IC7") (pin "30") (pinfunction "A5_30") (pintype "input"))
      (node (ref "IC8") (pin "30") (pinfunction "A5_30") (pintype "input"))
      (node (ref "RAMCPLD") (pin "13") (pinfunction "PB2/15_13") (pintype "input"))
    )
    (net (code "42") (name "ARAM6") (class "Default")
      (node (ref "IC7") (pin "31") (pinfunction "A6_31") (pintype "input"))
      (node (ref "IC8") (pin "31") (pinfunction "A6_31") (pintype "input"))
      (node (ref "RAMCPLD") (pin "12") (pinfunction "PB2/13_12") (pintype "input"))
    )
    (net (code "43") (name "ARAM7") (class "Default")
      (node (ref "IC7") (pin "32") (pinfunction "A7_32") (pintype "input"))
      (node (ref "IC8") (pin "32") (pinfunction "A7_32") (pintype "input"))
      (node (ref "RAMCPLD") (pin "11") (pinfunction "PB2/14_11") (pintype "input"))
    )
    (net (code "44") (name "ARAM8") (class "Default")
      (node (ref "IC7") (pin "33") (pinfunction "A8_33") (pintype "input"))
      (node (ref "IC8") (pin "33") (pinfunction "A8_33") (pintype "input"))
      (node (ref "RAMCPLD") (pin "10") (pinfunction "PB2/12_10") (pintype "input"))
    )
    (net (code "45") (name "ARAM9") (class "Default")
      (node (ref "IC7") (pin "34") (pinfunction "A9_34") (pintype "input"))
      (node (ref "IC8") (pin "34") (pinfunction "A9_34") (pintype "input"))
      (node (ref "RAMCPLD") (pin "9") (pinfunction "PB2/11_9") (pintype "input"))
    )
    (net (code "46") (name "ARAM10") (class "Default")
      (node (ref "IC7") (pin "22") (pinfunction "A10_22") (pintype "input"))
      (node (ref "IC8") (pin "22") (pinfunction "A10_22") (pintype "input"))
      (node (ref "RAMCPLD") (pin "24") (pinfunction "PB1/11_24") (pintype "input"))
    )
    (net (code "47") (name "ARAM11") (class "Default")
      (node (ref "IC7") (pin "35") (pinfunction "A11_35") (pintype "input"))
      (node (ref "IC8") (pin "35") (pinfunction "A11_35") (pintype "input"))
      (node (ref "RAMCPLD") (pin "7") (pinfunction "PB2/10_7") (pintype "input"))
    )
    (net (code "48") (name "ARAM12") (class "Default")
      (node (ref "IC7") (pin "36") (pinfunction "A12_36") (pintype "input"))
      (node (ref "IC8") (pin "36") (pinfunction "A12_36") (pintype "input"))
      (node (ref "RAMCPLD") (pin "6") (pinfunction "PB2/9_6") (pintype "input"))
    )
    (net (code "49") (name "AS20") (class "Default")
      (node (ref "CN1") (pin "P$91") (pinfunction "~{AS}_P91_P$91") (pintype "bidirectional"))
      (node (ref "RAMCPLD") (pin "140") (pinfunction "PB4/17_140") (pintype "input"))
    )
    (net (code "50") (name "AS30") (class "Default")
      (node (ref "IC2") (pin "J02") (pinfunction "AS_J02") (pintype "output"))
      (node (ref "RAMCPLD") (pin "132") (pinfunction "PB4/11_132") (pintype "input"))
      (node (ref "RN3") (pin "3") (pinfunction "3_3") (pintype "passive"))
    )
    (net (code "51") (name "AVEC") (class "Default")
      (node (ref "CN1") (pin "P$96") (pinfunction "~{AVEC}_P96_P$96") (pintype "bidirectional"))
      (node (ref "IC2") (pin "E02") (pinfunction "AVEC_E02") (pintype "input"))
    )
    (net (code "52") (name "BA0") (class "Default")
      (node (ref "IC7") (pin "21") (pinfunction "BA1_21") (pintype "input"))
      (node (ref "IC8") (pin "21") (pinfunction "BA1_21") (pintype "input"))
      (node (ref "RAMCPLD") (pin "23") (pinfunction "PB1/1_23") (pintype "input"))
    )
    (net (code "53") (name "BA1") (class "Default")
      (node (ref "IC7") (pin "20") (pinfunction "BAO_20") (pintype "input"))
      (node (ref "IC8") (pin "20") (pinfunction "BAO_20") (pintype "input"))
      (node (ref "RAMCPLD") (pin "22") (pinfunction "PB1/9_22") (pintype "input"))
    )
    (net (code "54") (name "BERR") (class "Default")
      (node (ref "CN1") (pin "P$94") (pinfunction "~{BERR}_P94_P$94") (pintype "bidirectional"))
      (node (ref "IC2") (pin "H01") (pinfunction "BERR_H01") (pintype "input"))
      (node (ref "RAMCPLD") (pin "75") (pinfunction "PB7/3_75") (pintype "input"))
    )
    (net (code "55") (name "BG20") (class "Default")
      (node (ref "CN1") (pin "P$112") (pinfunction "~{BG}_P112_P$112") (pintype "bidirectional"))
    )
    (net (code "56") (name "BG30") (class "Default")
      (node (ref "IC2") (pin "B02") (pinfunction "BG_B02") (pintype "output"))
      (node (ref "RAMCPLD") (pin "86") (pinfunction "PB7/14_86") (pintype "input"))
      (node (ref "RN3") (pin "4") (pinfunction "4_4") (pintype "passive"))
    )
    (net (code "57") (name "BGACK30") (class "Default")
      (node (ref "IC2") (pin "C03") (pinfunction "BGACK_C03") (pintype "input"))
      (node (ref "RAMCPLD") (pin "92") (pinfunction "PB8/5_92") (pintype "input"))
    )
    (net (code "58") (name "BR20") (class "Default")
      (node (ref "CN1") (pin "P$111") (pinfunction "~{BR}_P111_P$111") (pintype "bidirectional"))
      (node (ref "CN1") (pin "P$114") (pinfunction "~{BOSS}_P114_P$114") (pintype "bidirectional"))
      (node (ref "ENABLE030") (pin "2") (pinfunction "2_2") (pintype "passive"))
      (node (ref "R2") (pin "1") (pinfunction "1_1") (pintype "passive"))
      (node (ref "RAMCPLD") (pin "33") (pinfunction "PB3/5_33") (pintype "input"))
    )
    (net (code "59") (name "BR30") (class "Default")
      (node (ref "IC2") (pin "A01") (pinfunction "BR_A01") (pintype "input"))
      (node (ref "RAMCPLD") (pin "83") (pinfunction "PB7/16_83") (pintype "input"))
    )
    (net (code "60") (name "CAS") (class "Default")
      (node (ref "IC7") (pin "17") (pinfunction "CAS#_17") (pintype "input"))
      (node (ref "IC8") (pin "17") (pinfunction "CAS#_17") (pintype "input"))
      (node (ref "RAMCPLD") (pin "19") (pinfunction "PB1/5_19") (pintype "input"))
    )
    (net (code "61") (name "CBACK") (class "Default")
      (node (ref "IC2") (pin "J01") (pinfunction "CBACK_J01") (pintype "input"))
      (node (ref "RAMCPLD") (pin "74") (pinfunction "PB7/5_74") (pintype "input"))
    )
    (net (code "62") (name "CBREQ") (class "Default")
      (node (ref "IC2") (pin "K01") (pinfunction "CBREQ_K01") (pintype "output"))
      (node (ref "RAMCPLD") (pin "68") (pinfunction "PB5/10_68") (pintype "input"))
    )
    (net (code "63") (name "CDIS") (class "Default")
      (node (ref "CDIS") (pin "2") (pinfunction "2_2") (pintype "passive"))
      (node (ref "IC2") (pin "H12") (pinfunction "CDIS_H12") (pintype "input"))
      (node (ref "RN2") (pin "4") (pinfunction "4_4") (pintype "passive"))
    )
    (net (code "64") (name "CFGOUT") (class "Default")
      (node (ref "CN1") (pin "P$145") (pinfunction "~{CFOUT}_P145_P$145") (pintype "bidirectional"))
      (node (ref "RAMCPLD") (pin "34") (pinfunction "PB3/6_34") (pintype "input"))
    )
    (net (code "65") (name "CIIN") (class "Default")
      (node (ref "IC2") (pin "L01") (pinfunction "CIIN_L01") (pintype "input"))
      (node (ref "RAMCPLD") (pin "69") (pinfunction "PB5/17_69") (pintype "input"))
    )
    (net (code "66") (name "CIIOUT") (class "Default")
      (node (ref "IC2") (pin "C02") (pinfunction "CIOUT_C02") (pintype "output"))
    )
    (net (code "67") (name "CLK14M") (class "Default")
      (node (ref "CN1") (pin "P$99") (pinfunction "CPU_CLK_P99_P$99") (pintype "bidirectional"))
      (node (ref "RAMCPLD") (pin "71") (pinfunction "PB7/2_71") (pintype "input"))
    )
    (net (code "68") (name "CLK100M") (class "Default")
      (node (ref "OSC2") (pin "3") (pinfunction "OUT_3") (pintype "output"))
      (node (ref "RAMCPLD") (pin "32") (pinfunction "PB3/2/GCK2_32") (pintype "input"))
      (node (ref "TP1") (pin "TP") (pinfunction "TP_TP") (pintype "input"))
    )
    (net (code "69") (name "CLKCPU") (class "Default")
      (node (ref "IC2") (pin "E01") (pinfunction "CLK_E01") (pintype "input"))
      (node (ref "RAMCPLD") (pin "80") (pinfunction "PB7/9_80") (pintype "input"))
    )
    (net (code "70") (name "CLKRAM") (class "Default")
      (node (ref "IC7") (pin "38") (pinfunction "CLK_38") (pintype "input"))
      (node (ref "IC8") (pin "38") (pinfunction "CLK_38") (pintype "input"))
      (node (ref "RAMCPLD") (pin "4") (pinfunction "PB2/4_4") (pintype "input"))
    )
    (net (code "71") (name "CLKRAME") (class "Default")
      (node (ref "IC7") (pin "37") (pinfunction "CKE_37") (pintype "input"))
      (node (ref "IC8") (pin "37") (pinfunction "CKE_37") (pintype "input"))
      (node (ref "RAMCPLD") (pin "5") (pinfunction "PB2/8_5") (pintype "input"))
    )
    (net (code "72") (name "D0") (class "Default")
      (node (ref "CN1") (pin "P$78") (pinfunction "D0_P78_P$78") (pintype "bidirectional"))
      (node (ref "IC2") (pin "K13") (pinfunction "D0_K13") (pintype "bidirectional"))
      (node (ref "U4") (pin "9") (pinfunction "A8_9") (pintype "bidirectional"))
    )
    (net (code "73") (name "D1") (class "Default")
      (node (ref "CN1") (pin "P$77") (pinfunction "D1_P77_P$77") (pintype "bidirectional"))
      (node (ref "IC2") (pin "K12") (pinfunction "D1_K12") (pintype "bidirectional"))
      (node (ref "U4") (pin "8") (pinfunction "A7_8") (pintype "bidirectional"))
    )
    (net (code "74") (name "D2") (class "Default")
      (node (ref "CN1") (pin "P$76") (pinfunction "D2_P76_P$76") (pintype "bidirectional"))
      (node (ref "IC2") (pin "L13") (pinfunction "D2_L13") (pintype "bidirectional"))
      (node (ref "U4") (pin "7") (pinfunction "A6_7") (pintype "bidirectional"))
    )
    (net (code "75") (name "D3") (class "Default")
      (node (ref "CN1") (pin "P$75") (pinfunction "D3_P75_P$75") (pintype "bidirectional"))
      (node (ref "IC2") (pin "M13") (pinfunction "D3_M13") (pintype "bidirectional"))
      (node (ref "U4") (pin "6") (pinfunction "A5_6") (pintype "bidirectional"))
    )
    (net (code "76") (name "D4") (class "Default")
      (node (ref "CN1") (pin "P$74") (pinfunction "D4_P74_P$74") (pintype "bidirectional"))
      (node (ref "IC2") (pin "L12") (pinfunction "D4_L12") (pintype "bidirectional"))
      (node (ref "U4") (pin "5") (pinfunction "A4_5") (pintype "bidirectional"))
    )
    (net (code "77") (name "D5") (class "Default")
      (node (ref "CN1") (pin "P$73") (pinfunction "D5_P73_P$73") (pintype "bidirectional"))
      (node (ref "IC2") (pin "K11") (pinfunction "D5_K11") (pintype "bidirectional"))
      (node (ref "U4") (pin "4") (pinfunction "A3_4") (pintype "bidirectional"))
    )
    (net (code "78") (name "D6") (class "Default")
      (node (ref "CN1") (pin "P$72") (pinfunction "D6_P72_P$72") (pintype "bidirectional"))
      (node (ref "IC2") (pin "M12") (pinfunction "D6_M12") (pintype "bidirectional"))
      (node (ref "U4") (pin "3") (pinfunction "A2_3") (pintype "bidirectional"))
    )
    (net (code "79") (name "D7") (class "Default")
      (node (ref "CN1") (pin "P$71") (pinfunction "D7_P71_P$71") (pintype "bidirectional"))
      (node (ref "IC2") (pin "L11") (pinfunction "D7_L11") (pintype "bidirectional"))
      (node (ref "U4") (pin "2") (pinfunction "A1_2") (pintype "bidirectional"))
    )
    (net (code "80") (name "D8") (class "Default")
      (node (ref "CN1") (pin "P$68") (pinfunction "D8_P68_P$68") (pintype "bidirectional"))
      (node (ref "IC2") (pin "N13") (pinfunction "D8_N13") (pintype "bidirectional"))
      (node (ref "U3") (pin "9") (pinfunction "A8_9") (pintype "bidirectional"))
    )
    (net (code "81") (name "D9") (class "Default")
      (node (ref "CN1") (pin "P$67") (pinfunction "D9_P67_P$67") (pintype "bidirectional"))
      (node (ref "IC2") (pin "M11") (pinfunction "D9_M11") (pintype "bidirectional"))
      (node (ref "U3") (pin "8") (pinfunction "A7_8") (pintype "bidirectional"))
    )
    (net (code "82") (name "D10") (class "Default")
      (node (ref "CN1") (pin "P$66") (pinfunction "D10_P66_P$66") (pintype "bidirectional"))
      (node (ref "IC2") (pin "L10") (pinfunction "D10_L10") (pintype "bidirectional"))
      (node (ref "U3") (pin "7") (pinfunction "A6_7") (pintype "bidirectional"))
    )
    (net (code "83") (name "D11") (class "Default")
      (node (ref "CN1") (pin "P$65") (pinfunction "D11_P65_P$65") (pintype "bidirectional"))
      (node (ref "IC2") (pin "N12") (pinfunction "D11_N12") (pintype "bidirectional"))
      (node (ref "U3") (pin "6") (pinfunction "A5_6") (pintype "bidirectional"))
    )
    (net (code "84") (name "D12") (class "Default")
      (node (ref "CN1") (pin "P$64") (pinfunction "D12_P64_P$64") (pintype "bidirectional"))
      (node (ref "IC2") (pin "M10") (pinfunction "D12_M10") (pintype "bidirectional"))
      (node (ref "U3") (pin "5") (pinfunction "A4_5") (pintype "bidirectional"))
    )
    (net (code "85") (name "D13") (class "Default")
      (node (ref "CN1") (pin "P$63") (pinfunction "D13_P63_P$63") (pintype "bidirectional"))
      (node (ref "IC2") (pin "N11") (pinfunction "D13_N11") (pintype "bidirectional"))
      (node (ref "U3") (pin "4") (pinfunction "A3_4") (pintype "bidirectional"))
    )
    (net (code "86") (name "D14") (class "Default")
      (node (ref "CN1") (pin "P$62") (pinfunction "D14_P62_P$62") (pintype "bidirectional"))
      (node (ref "IC2") (pin "M09") (pinfunction "D14_M09") (pintype "bidirectional"))
      (node (ref "U3") (pin "3") (pinfunction "A2_3") (pintype "bidirectional"))
    )
    (net (code "87") (name "D15") (class "Default")
      (node (ref "CN1") (pin "P$61") (pinfunction "D15_P61_P$61") (pintype "bidirectional"))
      (node (ref "IC2") (pin "N10") (pinfunction "D15_N10") (pintype "bidirectional"))
      (node (ref "U3") (pin "2") (pinfunction "A1_2") (pintype "bidirectional"))
    )
    (net (code "88") (name "D16") (class "Default")
      (node (ref "CN1") (pin "P$58") (pinfunction "D16_P58_P$58") (pintype "bidirectional"))
      (node (ref "IC2") (pin "N09") (pinfunction "D16_N09") (pintype "bidirectional"))
      (node (ref "IDE") (pin "4") (pinfunction "S_4") (pintype "passive"))
      (node (ref "U2") (pin "9") (pinfunction "A8_9") (pintype "bidirectional"))
    )
    (net (code "89") (name "D17") (class "Default")
      (node (ref "CN1") (pin "P$57") (pinfunction "D17_P57_P$57") (pintype "bidirectional"))
      (node (ref "IC2") (pin "M08") (pinfunction "D17_M08") (pintype "bidirectional"))
      (node (ref "IDE") (pin "6") (pinfunction "S_6") (pintype "passive"))
      (node (ref "U2") (pin "8") (pinfunction "A7_8") (pintype "bidirectional"))
    )
    (net (code "90") (name "D18") (class "Default")
      (node (ref "CN1") (pin "P$56") (pinfunction "D18_P56_P$56") (pintype "bidirectional"))
      (node (ref "IC2") (pin "N08") (pinfunction "D18_N08") (pintype "bidirectional"))
      (node (ref "IDE") (pin "8") (pinfunction "S_8") (pintype "passive"))
      (node (ref "U2") (pin "7") (pinfunction "A6_7") (pintype "bidirectional"))
    )
    (net (code "91") (name "D19") (class "Default")
      (node (ref "CN1") (pin "P$55") (pinfunction "D19_P55_P$55") (pintype "bidirectional"))
      (node (ref "IC2") (pin "N07") (pinfunction "D19_N07") (pintype "bidirectional"))
      (node (ref "IDE") (pin "10") (pinfunction "S_10") (pintype "passive"))
      (node (ref "U2") (pin "6") (pinfunction "A5_6") (pintype "bidirectional"))
    )
    (net (code "92") (name "D20") (class "Default")
      (node (ref "CN1") (pin "P$54") (pinfunction "D20_P54_P$54") (pintype "bidirectional"))
      (node (ref "IC2") (pin "M07") (pinfunction "D20_M07") (pintype "bidirectional"))
      (node (ref "IDE") (pin "12") (pinfunction "S_12") (pintype "passive"))
      (node (ref "U2") (pin "5") (pinfunction "A4_5") (pintype "bidirectional"))
    )
    (net (code "93") (name "D21") (class "Default")
      (node (ref "CN1") (pin "P$53") (pinfunction "D21_P53_P$53") (pintype "bidirectional"))
      (node (ref "IC2") (pin "N06") (pinfunction "D21_N06") (pintype "bidirectional"))
      (node (ref "IDE") (pin "14") (pinfunction "S_14") (pintype "passive"))
      (node (ref "U2") (pin "4") (pinfunction "A3_4") (pintype "bidirectional"))
    )
    (net (code "94") (name "D22") (class "Default")
      (node (ref "CN1") (pin "P$52") (pinfunction "D22_P52_P$52") (pintype "bidirectional"))
      (node (ref "IC2") (pin "M06") (pinfunction "D22_M06") (pintype "bidirectional"))
      (node (ref "IDE") (pin "16") (pinfunction "S_16") (pintype "passive"))
      (node (ref "U2") (pin "3") (pinfunction "A2_3") (pintype "bidirectional"))
    )
    (net (code "95") (name "D23") (class "Default")
      (node (ref "CN1") (pin "P$51") (pinfunction "D23_P51_P$51") (pintype "bidirectional"))
      (node (ref "IC2") (pin "N05") (pinfunction "D23_N05") (pintype "bidirectional"))
      (node (ref "IDE") (pin "18") (pinfunction "S_18") (pintype "passive"))
      (node (ref "U2") (pin "2") (pinfunction "A1_2") (pintype "bidirectional"))
    )
    (net (code "96") (name "D24") (class "Default")
      (node (ref "CN1") (pin "P$48") (pinfunction "D24_P48_P$48") (pintype "bidirectional"))
      (node (ref "IC2") (pin "M05") (pinfunction "D24_M05") (pintype "bidirectional"))
      (node (ref "IDE") (pin "17") (pinfunction "S_17") (pintype "passive"))
      (node (ref "RAMCPLD") (pin "52") (pinfunction "PB5/2_52") (pintype "input"))
      (node (ref "U1") (pin "9") (pinfunction "A8_9") (pintype "bidirectional"))
    )
    (net (code "97") (name "D25") (class "Default")
      (node (ref "CN1") (pin "P$47") (pinfunction "D25_P47_P$47") (pintype "bidirectional"))
      (node (ref "IC2") (pin "N04") (pinfunction "D25_N04") (pintype "bidirectional"))
      (node (ref "IDE") (pin "15") (pinfunction "S_15") (pintype "passive"))
      (node (ref "RAMCPLD") (pin "51") (pinfunction "PB3/17_51") (pintype "input"))
      (node (ref "U1") (pin "8") (pinfunction "A7_8") (pintype "bidirectional"))
    )
    (net (code "98") (name "D26") (class "Default")
      (node (ref "CN1") (pin "P$46") (pinfunction "D26_P46_P$46") (pintype "bidirectional"))
      (node (ref "IC2") (pin "N03") (pinfunction "D26_N03") (pintype "bidirectional"))
      (node (ref "IDE") (pin "13") (pinfunction "S_13") (pintype "passive"))
      (node (ref "RAMCPLD") (pin "50") (pinfunction "PB3/15_50") (pintype "input"))
      (node (ref "U1") (pin "7") (pinfunction "A6_7") (pintype "bidirectional"))
    )
    (net (code "99") (name "D27") (class "Default")
      (node (ref "CN1") (pin "P$45") (pinfunction "D27_P45_P$45") (pintype "bidirectional"))
      (node (ref "IC2") (pin "M04") (pinfunction "D27_M04") (pintype "bidirectional"))
      (node (ref "IDE") (pin "11") (pinfunction "S_11") (pintype "passive"))
      (node (ref "RAMCPLD") (pin "49") (pinfunction "PB3/14_49") (pintype "input"))
      (node (ref "U1") (pin "6") (pinfunction "A5_6") (pintype "bidirectional"))
    )
    (net (code "100") (name "D28") (class "Default")
      (node (ref "CN1") (pin "P$44") (pinfunction "D28_P44_P$44") (pintype "bidirectional"))
      (node (ref "IC2") (pin "N02") (pinfunction "D28_N02") (pintype "bidirectional"))
      (node (ref "IDE") (pin "9") (pinfunction "S_9") (pintype "passive"))
      (node (ref "RAMCPLD") (pin "48") (pinfunction "PB3/10_48") (pintype "input"))
      (node (ref "U1") (pin "5") (pinfunction "A4_5") (pintype "bidirectional"))
    )
    (net (code "101") (name "D29") (class "Default")
      (node (ref "CN1") (pin "P$43") (pinfunction "D29_P43_P$43") (pintype "bidirectional"))
      (node (ref "IC2") (pin "M03") (pinfunction "D29_M03") (pintype "bidirectional"))
      (node (ref "IDE") (pin "7") (pinfunction "S_7") (pintype "passive"))
      (node (ref "RAMCPLD") (pin "46") (pinfunction "PB3/7_46") (pintype "input"))
      (node (ref "U1") (pin "4") (pinfunction "A3_4") (pintype "bidirectional"))
    )
    (net (code "102") (name "D30") (class "Default")
      (node (ref "CN1") (pin "P$42") (pinfunction "D30_P42_P$42") (pintype "bidirectional"))
      (node (ref "IC2") (pin "L04") (pinfunction "D30_L04") (pintype "bidirectional"))
      (node (ref "IDE") (pin "5") (pinfunction "S_5") (pintype "passive"))
      (node (ref "RAMCPLD") (pin "45") (pinfunction "PB3/12_45") (pintype "input"))
      (node (ref "U1") (pin "3") (pinfunction "A2_3") (pintype "bidirectional"))
    )
    (net (code "103") (name "D31") (class "Default")
      (node (ref "CN1") (pin "P$41") (pinfunction "D31_P41_P$41") (pintype "bidirectional"))
      (node (ref "IC2") (pin "N01") (pinfunction "D31_N01") (pintype "bidirectional"))
      (node (ref "IDE") (pin "3") (pinfunction "S_3") (pintype "passive"))
      (node (ref "RAMCPLD") (pin "44") (pinfunction "PB3/4_44") (pintype "input"))
      (node (ref "U1") (pin "2") (pinfunction "A1_2") (pintype "bidirectional"))
    )
    (net (code "104") (name "DBEN") (class "Default")
      (node (ref "IC2") (pin "M01") (pinfunction "DBEN_M01") (pintype "output"))
    )
    (net (code "105") (name "DQM0") (class "Default")
      (node (ref "IC8") (pin "15") (pinfunction "DQML_15") (pintype "input"))
      (node (ref "RAMCPLD") (pin "16") (pinfunction "PB1/2_16") (pintype "input"))
    )
    (net (code "106") (name "DQM1") (class "Default")
      (node (ref "IC8") (pin "39") (pinfunction "DQMH_39") (pintype "input"))
      (node (ref "RAMCPLD") (pin "31") (pinfunction "PB1/10_31") (pintype "input"))
    )
    (net (code "107") (name "DQM2") (class "Default")
      (node (ref "IC7") (pin "15") (pinfunction "DQML_15") (pintype "input"))
      (node (ref "RAMCPLD") (pin "15") (pinfunction "PB2/17_15") (pintype "input"))
    )
    (net (code "108") (name "DQM3") (class "Default")
      (node (ref "IC7") (pin "39") (pinfunction "DQMH_39") (pintype "input"))
      (node (ref "RAMCPLD") (pin "3") (pinfunction "PB2/6_3") (pintype "input"))
    )
    (net (code "109") (name "DRAM0") (class "Default")
      (node (ref "IC8") (pin "2") (pinfunction "DRAMO_2") (pintype "input"))
      (node (ref "U4") (pin "11") (pinfunction "B8_11") (pintype "bidirectional"))
    )
    (net (code "110") (name "DRAM1") (class "Default")
      (node (ref "IC8") (pin "4") (pinfunction "DRAM1_4") (pintype "input"))
      (node (ref "U4") (pin "12") (pinfunction "B7_12") (pintype "bidirectional"))
    )
    (net (code "111") (name "DRAM2") (class "Default")
      (node (ref "IC8") (pin "5") (pinfunction "DRAM2_5") (pintype "input"))
      (node (ref "U4") (pin "13") (pinfunction "B6_13") (pintype "bidirectional"))
    )
    (net (code "112") (name "DRAM3") (class "Default")
      (node (ref "IC8") (pin "7") (pinfunction "DRAM3_7") (pintype "input"))
      (node (ref "U4") (pin "14") (pinfunction "B5_14") (pintype "bidirectional"))
    )
    (net (code "113") (name "DRAM4") (class "Default")
      (node (ref "IC8") (pin "8") (pinfunction "DRAM4_8") (pintype "input"))
      (node (ref "U4") (pin "15") (pinfunction "B4_15") (pintype "bidirectional"))
    )
    (net (code "114") (name "DRAM5") (class "Default")
      (node (ref "IC8") (pin "10") (pinfunction "DRAM5_10") (pintype "input"))
      (node (ref "U4") (pin "16") (pinfunction "B3_16") (pintype "bidirectional"))
    )
    (net (code "115") (name "DRAM6") (class "Default")
      (node (ref "IC8") (pin "11") (pinfunction "DRAM6_11") (pintype "input"))
      (node (ref "U4") (pin "17") (pinfunction "B2_17") (pintype "bidirectional"))
    )
    (net (code "116") (name "DRAM7") (class "Default")
      (node (ref "IC8") (pin "13") (pinfunction "DRAM7_13") (pintype "input"))
      (node (ref "U4") (pin "18") (pinfunction "B1_18") (pintype "bidirectional"))
    )
    (net (code "117") (name "DRAM8") (class "Default")
      (node (ref "IC8") (pin "42") (pinfunction "DRAM8_42") (pintype "input"))
      (node (ref "U3") (pin "11") (pinfunction "B8_11") (pintype "bidirectional"))
    )
    (net (code "118") (name "DRAM9") (class "Default")
      (node (ref "IC8") (pin "44") (pinfunction "DRAM9_44") (pintype "input"))
      (node (ref "U3") (pin "12") (pinfunction "B7_12") (pintype "bidirectional"))
    )
    (net (code "119") (name "DRAM10") (class "Default")
      (node (ref "IC8") (pin "45") (pinfunction "DRAM10_45") (pintype "input"))
      (node (ref "U3") (pin "13") (pinfunction "B6_13") (pintype "bidirectional"))
    )
    (net (code "120") (name "DRAM11") (class "Default")
      (node (ref "IC8") (pin "47") (pinfunction "DRAM11_47") (pintype "input"))
      (node (ref "U3") (pin "14") (pinfunction "B5_14") (pintype "bidirectional"))
    )
    (net (code "121") (name "DRAM12") (class "Default")
      (node (ref "IC8") (pin "48") (pinfunction "DRAM12_48") (pintype "input"))
      (node (ref "U3") (pin "15") (pinfunction "B4_15") (pintype "bidirectional"))
    )
    (net (code "122") (name "DRAM13") (class "Default")
      (node (ref "IC8") (pin "50") (pinfunction "DRAM13_50") (pintype "input"))
      (node (ref "U3") (pin "16") (pinfunction "B3_16") (pintype "bidirectional"))
    )
    (net (code "123") (name "DRAM14") (class "Default")
      (node (ref "IC8") (pin "51") (pinfunction "DQM_51") (pintype "input"))
      (node (ref "U3") (pin "17") (pinfunction "B2_17") (pintype "bidirectional"))
    )
    (net (code "124") (name "DRAM15") (class "Default")
      (node (ref "IC8") (pin "53") (pinfunction "DRAM15_53") (pintype "input"))
      (node (ref "U3") (pin "18") (pinfunction "B1_18") (pintype "bidirectional"))
    )
    (net (code "125") (name "DRAM16") (class "Default")
      (node (ref "IC7") (pin "2") (pinfunction "DRAMO_2") (pintype "input"))
      (node (ref "U2") (pin "11") (pinfunction "B8_11") (pintype "bidirectional"))
    )
    (net (code "126") (name "DRAM17") (class "Default")
      (node (ref "IC7") (pin "4") (pinfunction "DRAM1_4") (pintype "input"))
      (node (ref "U2") (pin "12") (pinfunction "B7_12") (pintype "bidirectional"))
    )
    (net (code "127") (name "DRAM18") (class "Default")
      (node (ref "IC7") (pin "5") (pinfunction "DRAM2_5") (pintype "input"))
      (node (ref "U2") (pin "13") (pinfunction "B6_13") (pintype "bidirectional"))
    )
    (net (code "128") (name "DRAM19") (class "Default")
      (node (ref "IC7") (pin "7") (pinfunction "DRAM3_7") (pintype "input"))
      (node (ref "U2") (pin "14") (pinfunction "B5_14") (pintype "bidirectional"))
    )
    (net (code "129") (name "DRAM20") (class "Default")
      (node (ref "IC7") (pin "8") (pinfunction "DRAM4_8") (pintype "input"))
      (node (ref "U2") (pin "15") (pinfunction "B4_15") (pintype "bidirectional"))
    )
    (net (code "130") (name "DRAM21") (class "Default")
      (node (ref "IC7") (pin "10") (pinfunction "DRAM5_10") (pintype "input"))
      (node (ref "U2") (pin "16") (pinfunction "B3_16") (pintype "bidirectional"))
    )
    (net (code "131") (name "DRAM22") (class "Default")
      (node (ref "IC7") (pin "11") (pinfunction "DRAM6_11") (pintype "input"))
      (node (ref "U2") (pin "17") (pinfunction "B2_17") (pintype "bidirectional"))
    )
    (net (code "132") (name "DRAM23") (class "Default")
      (node (ref "IC7") (pin "13") (pinfunction "DRAM7_13") (pintype "input"))
      (node (ref "U2") (pin "18") (pinfunction "B1_18") (pintype "bidirectional"))
    )
    (net (code "133") (name "DRAM24") (class "Default")
      (node (ref "IC7") (pin "42") (pinfunction "DRAM8_42") (pintype "input"))
      (node (ref "U1") (pin "11") (pinfunction "B8_11") (pintype "bidirectional"))
    )
    (net (code "134") (name "DRAM25") (class "Default")
      (node (ref "IC7") (pin "44") (pinfunction "DRAM9_44") (pintype "input"))
      (node (ref "U1") (pin "12") (pinfunction "B7_12") (pintype "bidirectional"))
    )
    (net (code "135") (name "DRAM26") (class "Default")
      (node (ref "IC7") (pin "45") (pinfunction "DRAM10_45") (pintype "input"))
      (node (ref "U1") (pin "13") (pinfunction "B6_13") (pintype "bidirectional"))
    )
    (net (code "136") (name "DRAM27") (class "Default")
      (node (ref "IC7") (pin "47") (pinfunction "DRAM11_47") (pintype "input"))
      (node (ref "U1") (pin "14") (pinfunction "B5_14") (pintype "bidirectional"))
    )
    (net (code "137") (name "DRAM28") (class "Default")
      (node (ref "IC7") (pin "48") (pinfunction "DRAM12_48") (pintype "input"))
      (node (ref "U1") (pin "15") (pinfunction "B4_15") (pintype "bidirectional"))
    )
    (net (code "138") (name "DRAM29") (class "Default")
      (node (ref "IC7") (pin "50") (pinfunction "DRAM13_50") (pintype "input"))
      (node (ref "U1") (pin "16") (pinfunction "B3_16") (pintype "bidirectional"))
    )
    (net (code "139") (name "DRAM30") (class "Default")
      (node (ref "IC7") (pin "51") (pinfunction "DQM_51") (pintype "input"))
      (node (ref "U1") (pin "17") (pinfunction "B2_17") (pintype "bidirectional"))
    )
    (net (code "140") (name "DRAM31") (class "Default")
      (node (ref "IC7") (pin "53") (pinfunction "DRAM15_53") (pintype "input"))
      (node (ref "U1") (pin "18") (pinfunction "B1_18") (pintype "bidirectional"))
    )
    (net (code "141") (name "DS20") (class "Default")
      (node (ref "CN1") (pin "P$92") (pinfunction "~{DS}_P92_P$92") (pintype "bidirectional"))
      (node (ref "RAMCPLD") (pin "139") (pinfunction "PB4/16_139") (pintype "input"))
    )
    (net (code "142") (name "DS30") (class "Default")
      (node (ref "IC2") (pin "K02") (pinfunction "DS_K02") (pintype "output"))
      (node (ref "RAMCPLD") (pin "133") (pinfunction "PB4/3_133") (pintype "input"))
      (node (ref "RN3") (pin "2") (pinfunction "2_2") (pintype "passive"))
    )
    (net (code "143") (name "DS30ACK0") (class "Default")
      (node (ref "IC2") (pin "F01") (pinfunction "DSACK0_F01") (pintype "input"))
      (node (ref "RAMCPLD") (pin "79") (pinfunction "PB7/10_79") (pintype "input"))
    )
    (net (code "144") (name "DS30ACK1") (class "Default")
      (node (ref "IC2") (pin "G02") (pinfunction "DSACK1_G02") (pintype "input"))
      (node (ref "RAMCPLD") (pin "78") (pinfunction "PB7/8_78") (pintype "input"))
    )
    (net (code "145") (name "DSACK0") (class "Default")
      (node (ref "CN1") (pin "P$98") (pinfunction "~{DSACK0}_P98_P$98") (pintype "bidirectional"))
      (node (ref "RAMCPLD") (pin "135") (pinfunction "PB4/10_135") (pintype "input"))
    )
    (net (code "146") (name "DSACK1") (class "Default")
      (node (ref "CN1") (pin "P$97") (pinfunction "~{DSACK1}_P97_P$97") (pintype "bidirectional"))
      (node (ref "RAMCPLD") (pin "136") (pinfunction "PB4/14_136") (pintype "input"))
    )
    (net (code "147") (name "E") (class "Default")
      (node (ref "CN1") (pin "P$100") (pinfunction "E_P100_P$100") (pintype "bidirectional"))
    )
    (net (code "148") (name "FC0") (class "Default")
      (node (ref "CN1") (pin "P$105") (pinfunction "FC0_P105_P$105") (pintype "bidirectional"))
      (node (ref "IC2") (pin "D02") (pinfunction "FC0_D02") (pintype "output"))
      (node (ref "RAMCPLD") (pin "85") (pinfunction "PB7/12_85") (pintype "input"))
    )
    (net (code "149") (name "FC1") (class "Default")
      (node (ref "CN1") (pin "P$104") (pinfunction "FC1_P104_P$104") (pintype "bidirectional"))
      (node (ref "IC2") (pin "C01") (pinfunction "FC1_C01") (pintype "output"))
      (node (ref "RAMCPLD") (pin "82") (pinfunction "PB7/11_82") (pintype "input"))
    )
    (net (code "150") (name "FC2") (class "Default")
      (node (ref "CN1") (pin "P$103") (pinfunction "FC2_P103_P$103") (pintype "bidirectional"))
      (node (ref "IC2") (pin "D01") (pinfunction "FC2_D01") (pintype "output"))
      (node (ref "RAMCPLD") (pin "81") (pinfunction "PB7/13_81") (pintype "input"))
    )
    (net (code "151") (name "GND") (class "Default")
      (node (ref "C1") (pin "2") (pinfunction "P$2_2") (pintype "passive"))
      (node (ref "C10") (pin "2") (pinfunction "2_2") (pintype "passive"))
      (node (ref "C11") (pin "2") (pinfunction "2_2") (pintype "passive"))
      (node (ref "C12") (pin "2") (pinfunction "2_2") (pintype "passive"))
      (node (ref "C13") (pin "2") (pinfunction "2_2") (pintype "passive"))
      (node (ref "C14") (pin "2") (pinfunction "2_2") (pintype "passive"))
      (node (ref "C15") (pin "2") (pinfunction "2_2") (pintype "passive"))
      (node (ref "C16") (pin "2") (pinfunction "P$2_2") (pintype "passive"))
      (node (ref "C19") (pin "2") (pinfunction "2_2") (pintype "passive"))
      (node (ref "C2") (pin "2") (pinfunction "P$2_2") (pintype "passive"))
      (node (ref "C21") (pin "2") (pinfunction "P$2_2") (pintype "passive"))
      (node (ref "C23") (pin "2") (pinfunction "2_2") (pintype "passive"))
      (node (ref "C28") (pin "2") (pinfunction "2_2") (pintype "passive"))
      (node (ref "C29") (pin "2") (pinfunction "P$2_2") (pintype "passive"))
      (node (ref "C34") (pin "2") (pinfunction "2_2") (pintype "passive"))
      (node (ref "C38") (pin "2") (pinfunction "2_2") (pintype "passive"))
      (node (ref "C39") (pin "1") (pinfunction "1_1") (pintype "passive"))
      (node (ref "C40") (pin "1") (pinfunction "1_1") (pintype "passive"))
      (node (ref "C41") (pin "1") (pinfunction "1_1") (pintype "passive"))
      (node (ref "C42") (pin "2") (pinfunction "2_2") (pintype "passive"))
      (node (ref "C43") (pin "1") (pinfunction "1_1") (pintype "passive"))
      (node (ref "C44") (pin "1") (pinfunction "1_1") (pintype "passive"))
      (node (ref "C45") (pin "1") (pinfunction "1_1") (pintype "passive"))
      (node (ref "C46") (pin "1") (pinfunction "1_1") (pintype "passive"))
      (node (ref "C47") (pin "1") (pinfunction "1_1") (pintype "passive"))
      (node (ref "C48") (pin "1") (pinfunction "1_1") (pintype "passive"))
      (node (ref "C49") (pin "1") (pinfunction "1_1") (pintype "passive"))
      (node (ref "C5") (pin "2") (pinfunction "2_2") (pintype "passive"))
      (node (ref "C50") (pin "2") (pinfunction "2_2") (pintype "passive"))
      (node (ref "C51") (pin "2") (pinfunction "2_2") (pintype "passive"))
      (node (ref "C52") (pin "2") (pinfunction "2_2") (pintype "passive"))
      (node (ref "C54") (pin "2") (pinfunction "P$2_2") (pintype "passive"))
      (node (ref "C58") (pin "1") (pinfunction "1_1") (pintype "passive"))
      (node (ref "C59") (pin "2") (pinfunction "2_2") (pintype "passive"))
      (node (ref "C6") (pin "2") (pinfunction "P$2_2") (pintype "passive"))
      (node (ref "C62") (pin "1") (pinfunction "1_1") (pintype "passive"))
      (node (ref "C63") (pin "1") (pinfunction "1_1") (pintype "passive"))
      (node (ref "C7") (pin "2") (pinfunction "2_2") (pintype "passive"))
      (node (ref "C76") (pin "2") (pinfunction "2_2") (pintype "passive"))
      (node (ref "C77") (pin "2") (pinfunction "2_2") (pintype "passive"))
      (node (ref "C8") (pin "2") (pinfunction "P$2_2") (pintype "passive"))
      (node (ref "C81") (pin "1") (pinfunction "1_1") (pintype "passive"))
      (node (ref "C83") (pin "2") (pinfunction "P$2_2") (pintype "passive"))
      (node (ref "C84") (pin "1") (pinfunction "P$1_1") (pintype "passive"))
      (node (ref "C85") (pin "1") (pinfunction "P$1_1") (pintype "passive"))
      (node (ref "C9") (pin "2") (pinfunction "P$2_2") (pintype "passive"))
      (node (ref "CDIS") (pin "1") (pinfunction "1_1") (pintype "passive"))
      (node (ref "CN1") (pin "P$101") (pinfunction "GND_P101_P$101") (pintype "bidirectional"))
      (node (ref "CN1") (pin "P$19") (pinfunction "GND_P19_P$19") (pintype "bidirectional"))
      (node (ref "CN1") (pin "P$29") (pinfunction "GND_P29_P$29") (pintype "bidirectional"))
      (node (ref "CN1") (pin "P$39") (pinfunction "GND_P39_P$39") (pintype "bidirectional"))
      (node (ref "CN1") (pin "P$49") (pinfunction "GND_P49_P$49") (pintype "bidirectional"))
      (node (ref "CN1") (pin "P$59") (pinfunction "GND_P59_P$59") (pintype "bidirectional"))
      (node (ref "CN1") (pin "P$69") (pinfunction "GND_P69_P$69") (pintype "bidirectional"))
      (node (ref "CN1") (pin "P$79") (pinfunction "GND_P79_P$79") (pintype "bidirectional"))
      (node (ref "CN1") (pin "P$9") (pinfunction "GND_P9_P$9") (pintype "bidirectional"))
      (node (ref "ENABLE030") (pin "1") (pinfunction "1_1") (pintype "passive"))
      (node (ref "IC1") (pin "1") (pinfunction "ADJ_1") (pintype "input"))
      (node (ref "IC7") (pin "12") (pinfunction "VSSQ(2)_12") (pintype "input"))
      (node (ref "IC7") (pin "28") (pinfunction "VSS(1)_28") (pintype "input"))
      (node (ref "IC7") (pin "41") (pinfunction "VSS(2)_41") (pintype "input"))
      (node (ref "IC7") (pin "46") (pinfunction "VSSQ(3)_46") (pintype "input"))
      (node (ref "IC7") (pin "52") (pinfunction "VSSQ(4)_52") (pintype "input"))
      (node (ref "IC7") (pin "54") (pinfunction "VSS(3)_54") (pintype "input"))
      (node (ref "IC7") (pin "6") (pinfunction "VSSQ(1)_6") (pintype "input"))
      (node (ref "IC8") (pin "12") (pinfunction "VSSQ(2)_12") (pintype "input"))
      (node (ref "IC8") (pin "28") (pinfunction "VSS(1)_28") (pintype "input"))
      (node (ref "IC8") (pin "41") (pinfunction "VSS(2)_41") (pintype "input"))
      (node (ref "IC8") (pin "46") (pinfunction "VSSQ(3)_46") (pintype "input"))
      (node (ref "IC8") (pin "52") (pinfunction "VSSQ(4)_52") (pintype "input"))
      (node (ref "IC8") (pin "54") (pinfunction "VSS(3)_54") (pintype "input"))
      (node (ref "IC8") (pin "6") (pinfunction "VSSQ(1)_6") (pintype "input"))
      (node (ref "IDE") (pin "19") (pinfunction "S_19") (pintype "passive"))
      (node (ref "IDE") (pin "2") (pinfunction "S_2") (pintype "passive"))
      (node (ref "IDE") (pin "22") (pinfunction "S_22") (pintype "passive"))
      (node (ref "IDE") (pin "24") (pinfunction "S_24") (pintype "passive"))
      (node (ref "IDE") (pin "26") (pinfunction "S_26") (pintype "passive"))
      (node (ref "IDE") (pin "30") (pinfunction "S_30") (pintype "passive"))
      (node (ref "IDE") (pin "40") (pinfunction "S_40") (pintype "passive"))
      (node (ref "IDE") (pin "43") (pinfunction "S_43") (pintype "passive"))
      (node (ref "IDE") (pin "44") (pinfunction "S_44") (pintype "passive"))
      (node (ref "JTAG1") (pin "5") (pinfunction "5_5") (pintype "passive"))
      (node (ref "MMUDIS") (pin "1") (pinfunction "1_1") (pintype "passive"))
      (node (ref "OSC2") (pin "2") (pinfunction "GND_2") (pintype "power_in"))
      (node (ref "PWR2") (pin "1") (pinfunction "1_1") (pintype "passive"))
      (node (ref "R5") (pin "2") (pinfunction "2_2") (pintype "passive"))
      (node (ref "RAMCPLD") (pin "108") (pinfunction "GND(10)_108") (pintype "input"))
      (node (ref "RAMCPLD") (pin "114") (pinfunction "GND(11)_114") (pintype "input"))
      (node (ref "RAMCPLD") (pin "123") (pinfunction "GND(12)_123") (pintype "input"))
      (node (ref "RAMCPLD") (pin "144") (pinfunction "GND(13)_144") (pintype "input"))
      (node (ref "RAMCPLD") (pin "18") (pinfunction "GND(1)_18") (pintype "input"))
      (node (ref "RAMCPLD") (pin "29") (pinfunction "GND(2)_29") (pintype "input"))
      (node (ref "RAMCPLD") (pin "36") (pinfunction "GND(3)_36") (pintype "input"))
      (node (ref "RAMCPLD") (pin "47") (pinfunction "GND(4)_47") (pintype "input"))
      (node (ref "RAMCPLD") (pin "62") (pinfunction "GND(5)_62") (pintype "input"))
      (node (ref "RAMCPLD") (pin "72") (pinfunction "GND(6)_72") (pintype "input"))
      (node (ref "RAMCPLD") (pin "89") (pinfunction "GND(7)_89") (pintype "input"))
      (node (ref "RAMCPLD") (pin "90") (pinfunction "GND(8)_90") (pintype "input"))
      (node (ref "RAMCPLD") (pin "99") (pinfunction "GND(9)_99") (pintype "input"))
      (node (ref "U1") (pin "10") (pinfunction "GND_10") (pintype "passive"))
      (node (ref "U2") (pin "10") (pinfunction "GND_10") (pintype "passive"))
      (node (ref "U3") (pin "10") (pinfunction "GND_10") (pintype "passive"))
      (node (ref "U4") (pin "10") (pinfunction "GND_10") (pintype "passive"))
    )
    (net (code "152") (name "HALT") (class "Default")
      (node (ref "IC2") (pin "H02") (pinfunction "HALT_H02") (pintype "input"))
      (node (ref "RAMCPLD") (pin "76") (pinfunction "PB7/6_76") (pintype "input"))
    )
    (net (code "153") (name "IDECS0") (class "Default")
      (node (ref "IDE") (pin "37") (pinfunction "S_37") (pintype "passive"))
      (node (ref "RAMCPLD") (pin "64") (pinfunction "PB5/15_64") (pintype "input"))
    )
    (net (code "154") (name "IDECS1") (class "Default")
      (node (ref "IDE") (pin "38") (pinfunction "S_38") (pintype "passive"))
      (node (ref "RAMCPLD") (pin "61") (pinfunction "PB5/14_61") (pintype "input"))
    )
    (net (code "155") (name "IDEINT") (class "Default")
      (node (ref "IDE") (pin "31") (pinfunction "S_31") (pintype "passive"))
      (node (ref "R5") (pin "1") (pinfunction "1_1") (pintype "passive"))
      (node (ref "RAMCPLD") (pin "57") (pinfunction "PB5/9_57") (pintype "input"))
    )
    (net (code "156") (name "IDEWAIT") (class "Default")
      (node (ref "IDE") (pin "27") (pinfunction "S_27") (pintype "passive"))
      (node (ref "R3") (pin "1") (pinfunction "1_1") (pintype "passive"))
      (node (ref "RAMCPLD") (pin "56") (pinfunction "PB5/8_56") (pintype "input"))
    )
    (net (code "157") (name "INT2") (class "Default")
      (node (ref "CN1") (pin "P$137") (pinfunction "~{INT2}_P137_P$137") (pintype "bidirectional"))
      (node (ref "RAMCPLD") (pin "143") (pinfunction "PB2/2_143") (pintype "input"))
    )
    (net (code "158") (name "INT6") (class "Default")
      (node (ref "CN1") (pin "P$138") (pinfunction "~{INT6}_P138_P$138") (pintype "bidirectional"))
    )
    (net (code "159") (name "IOR") (class "Default")
      (node (ref "IDE") (pin "25") (pinfunction "S_25") (pintype "passive"))
      (node (ref "RAMCPLD") (pin "54") (pinfunction "PB5/6_54") (pintype "input"))
    )
    (net (code "160") (name "IOW") (class "Default")
      (node (ref "IDE") (pin "23") (pinfunction "S_23") (pintype "passive"))
      (node (ref "RAMCPLD") (pin "53") (pinfunction "PB5/5_53") (pintype "input"))
    )
    (net (code "161") (name "IPL0") (class "Default")
      (node (ref "CN1") (pin "P$83") (pinfunction "IPL0_P83_P$83") (pintype "bidirectional"))
      (node (ref "IC2") (pin "H13") (pinfunction "IPL0_H13") (pintype "input"))
    )
    (net (code "162") (name "IPL1") (class "Default")
      (node (ref "CN1") (pin "P$82") (pinfunction "IPL1_P82_P$82") (pintype "bidirectional"))
      (node (ref "IC2") (pin "G13") (pinfunction "IPL1_G13") (pintype "input"))
    )
    (net (code "163") (name "IPL2") (class "Default")
      (node (ref "CN1") (pin "P$81") (pinfunction "ILP2_P81_P$81") (pintype "bidirectional"))
      (node (ref "IC2") (pin "G12") (pinfunction "IPL2_G12") (pintype "input"))
    )
    (net (code "164") (name "MMUDIS") (class "Default")
      (node (ref "IC2") (pin "F13") (pinfunction "MMUDIS_F13") (pintype "input"))
      (node (ref "MMUDIS") (pin "2") (pinfunction "2_2") (pintype "passive"))
      (node (ref "RN2") (pin "1") (pinfunction "1_1") (pintype "passive"))
    )
    (net (code "165") (name "PUNT") (class "Default")
      (node (ref "CN1") (pin "P$133") (pinfunction "~{OVR}_P133_P$133") (pintype "bidirectional"))
      (node (ref "RAMCPLD") (pin "142") (pinfunction "PB2/1_142") (pintype "input"))
    )
    (net (code "166") (name "RAMCS") (class "Default")
      (node (ref "IC7") (pin "19") (pinfunction "CS#_19") (pintype "input"))
      (node (ref "IC8") (pin "19") (pinfunction "CS#_19") (pintype "input"))
      (node (ref "RAMCPLD") (pin "21") (pinfunction "PB1/8_21") (pintype "input"))
    )
    (net (code "167") (name "RAMOE") (class "Default")
      (node (ref "RAMCPLD") (pin "2") (pinfunction "PB2/5_2") (pintype "input"))
      (node (ref "U1") (pin "19") (pinfunction "~{OE}_19") (pintype "input"))
      (node (ref "U2") (pin "19") (pinfunction "~{OE}_19") (pintype "input"))
      (node (ref "U3") (pin "19") (pinfunction "~{OE}_19") (pintype "input"))
      (node (ref "U4") (pin "19") (pinfunction "~{OE}_19") (pintype "input"))
    )
    (net (code "168") (name "RAMWE") (class "Default")
      (node (ref "IC7") (pin "16") (pinfunction "WE#_16") (pintype "input"))
      (node (ref "IC8") (pin "16") (pinfunction "WE#_16") (pintype "input"))
      (node (ref "RAMCPLD") (pin "17") (pinfunction "PB1/3_17") (pintype "input"))
    )
    (net (code "169") (name "RAS") (class "Default")
      (node (ref "IC7") (pin "18") (pinfunction "RAS#_18") (pintype "input"))
      (node (ref "IC8") (pin "18") (pinfunction "RAS#_18") (pintype "input"))
      (node (ref "RAMCPLD") (pin "20") (pinfunction "PB1/6_20") (pintype "input"))
    )
    (net (code "170") (name "REFILL") (class "Default")
      (node (ref "IC2") (pin "J13") (pinfunction "REFILL_J13") (pintype "output"))
    )
    (net (code "171") (name "RESET") (class "Default")
      (node (ref "CN1") (pin "P$118") (pinfunction "~{RESET}_P118_P$118") (pintype "bidirectional"))
      (node (ref "IDE") (pin "1") (pinfunction "S_1") (pintype "passive"))
      (node (ref "RAMCPLD") (pin "43") (pinfunction "PB3/11_43") (pintype "input"))
    )
    (net (code "172") (name "RESET_O") (class "Default")
      (node (ref "CN1") (pin "P$85") (pinfunction "~{RST}_P85_P$85") (pintype "bidirectional"))
      (node (ref "R1") (pin "2") (pinfunction "2_2") (pintype "passive"))
    )
    (net (code "173") (name "RSTO") (class "Default")
      (node (ref "IC2") (pin "F12") (pinfunction "RESET_F12") (pintype "bidirectional"))
      (node (ref "R1") (pin "1") (pinfunction "1_1") (pintype "passive"))
      (node (ref "RAMCPLD") (pin "129") (pinfunction "PB4/6_129") (pintype "input"))
    )
    (net (code "174") (name "RW20") (class "Default")
      (node (ref "CN1") (pin "P$93") (pinfunction "RW_P93_P$93") (pintype "bidirectional"))
      (node (ref "RAMCPLD") (pin "138") (pinfunction "PB4/15_138") (pintype "input"))
    )
    (net (code "175") (name "RW30") (class "Default")
      (node (ref "IC2") (pin "L03") (pinfunction "R/~{W}_L03") (pintype "output"))
      (node (ref "RAMCPLD") (pin "134") (pinfunction "PB4/12_134") (pintype "input"))
      (node (ref "RN3") (pin "1") (pinfunction "1_1") (pintype "passive"))
    )
    (net (code "176") (name "RXD") (class "Default")
      (node (ref "CN1") (pin "P$143") (pinfunction "~{XRXD}_P143_P$143") (pintype "bidirectional"))
    )
    (net (code "177") (name "SIZ0") (class "Default")
      (node (ref "CN1") (pin "P$90") (pinfunction "SIZ0_P90_P$90") (pintype "bidirectional"))
      (node (ref "IC2") (pin "L02") (pinfunction "SIZ0_L02") (pintype "output"))
      (node (ref "RAMCPLD") (pin "66") (pinfunction "PB5/7_66") (pintype "input"))
    )
    (net (code "178") (name "SIZ1") (class "Default")
      (node (ref "CN1") (pin "P$89") (pinfunction "SIZ1_P89_P$89") (pintype "bidirectional"))
      (node (ref "IC2") (pin "K03") (pinfunction "SIZ1_K03") (pintype "output"))
      (node (ref "RAMCPLD") (pin "70") (pinfunction "PB5/13_70") (pintype "input"))
    )
    (net (code "179") (name "STATUS") (class "Default")
      (node (ref "IC2") (pin "J12") (pinfunction "STATUS_J12") (pintype "output"))
    )
    (net (code "180") (name "STERM") (class "Default")
      (node (ref "IC2") (pin "G01") (pinfunction "STERM_G01") (pintype "input"))
      (node (ref "RAMCPLD") (pin "77") (pinfunction "PB7/7_77") (pintype "input"))
    )
    (net (code "181") (name "TCK") (class "Default")
      (node (ref "JTAG1") (pin "4") (pinfunction "4_4") (pintype "passive"))
      (node (ref "RAMCPLD") (pin "67") (pinfunction "TCK_67") (pintype "input"))
    )
    (net (code "182") (name "TDI") (class "Default")
      (node (ref "JTAG1") (pin "2") (pinfunction "2_2") (pintype "passive"))
      (node (ref "RAMCPLD") (pin "63") (pinfunction "TDI_63") (pintype "input"))
    )
    (net (code "183") (name "TDO") (class "Default")
      (node (ref "JTAG1") (pin "3") (pinfunction "3_3") (pintype "passive"))
      (node (ref "RAMCPLD") (pin "122") (pinfunction "TDO_122") (pintype "input"))
    )
    (net (code "184") (name "TMS") (class "Default")
      (node (ref "JTAG1") (pin "1") (pinfunction "1_1") (pintype "passive"))
      (node (ref "RAMCPLD") (pin "65") (pinfunction "TMS_65") (pintype "input"))
    )
    (net (code "185") (name "TXD") (class "Default")
      (node (ref "CN1") (pin "P$144") (pinfunction "~{XTXD}_P144_P$144") (pintype "bidirectional"))
    )
    (net (code "186") (name "VCC") (class "Default")
      (node (ref "C12") (pin "1") (pinfunction "1_1") (pintype "passive"))
      (node (ref "C13") (pin "1") (pinfunction "1_1") (pintype "passive"))
      (node (ref "C14") (pin "1") (pinfunction "1_1") (pintype "passive"))
      (node (ref "C15") (pin "1") (pinfunction "1_1") (pintype "passive"))
      (node (ref "C16") (pin "1") (pinfunction "P$1_1") (pintype "passive"))
      (node (ref "C2") (pin "1") (pinfunction "P$1_1") (pintype "passive"))
      (node (ref "C28") (pin "1") (pinfunction "1_1") (pintype "passive"))
      (node (ref "C29") (pin "1") (pinfunction "P$1_1") (pintype "passive"))
      (node (ref "C50") (pin "1") (pinfunction "1_1") (pintype "passive"))
      (node (ref "C51") (pin "1") (pinfunction "1_1") (pintype "passive"))
      (node (ref "C52") (pin "1") (pinfunction "1_1") (pintype "passive"))
      (node (ref "C54") (pin "1") (pinfunction "P$1_1") (pintype "passive"))
      (node (ref "C59") (pin "1") (pinfunction "1_1") (pintype "passive"))
      (node (ref "C77") (pin "1") (pinfunction "1_1") (pintype "passive"))
      (node (ref "C83") (pin "1") (pinfunction "P$1_1") (pintype "passive"))
      (node (ref "CN1") (pin "P$10") (pinfunction "VCC_P10_P$10") (pintype "bidirectional"))
      (node (ref "CN1") (pin "P$102") (pinfunction "VCC_P102_P$102") (pintype "bidirectional"))
      (node (ref "CN1") (pin "P$120") (pinfunction "VCC_P120_P$120") (pintype "bidirectional"))
      (node (ref "CN1") (pin "P$20") (pinfunction "VCC_P20_P$20") (pintype "bidirectional"))
      (node (ref "CN1") (pin "P$30") (pinfunction "VCC_P30_P$30") (pintype "bidirectional"))
      (node (ref "CN1") (pin "P$40") (pinfunction "VCC_P40_P$40") (pintype "bidirectional"))
      (node (ref "CN1") (pin "P$50") (pinfunction "VCC_P50_P$50") (pintype "bidirectional"))
      (node (ref "CN1") (pin "P$60") (pinfunction "VCC_P60_P$60") (pintype "bidirectional"))
      (node (ref "CN1") (pin "P$70") (pinfunction "VCC_P70_P$70") (pintype "bidirectional"))
      (node (ref "CN1") (pin "P$80") (pinfunction "VCC_P80_P$80") (pintype "bidirectional"))
      (node (ref "IC1") (pin "3") (pinfunction "IN_3") (pintype "input"))
      (node (ref "IDE") (pin "41") (pinfunction "S_41") (pintype "passive"))
      (node (ref "IDE") (pin "42") (pinfunction "S_42") (pintype "passive"))
      (node (ref "PWR2") (pin "2") (pinfunction "2_2") (pintype "passive"))
      (node (ref "R2") (pin "2") (pinfunction "2_2") (pintype "passive"))
      (node (ref "R3") (pin "2") (pinfunction "2_2") (pintype "passive"))
      (node (ref "RN2") (pin "5") (pinfunction "5_5") (pintype "passive"))
      (node (ref "RN2") (pin "6") (pinfunction "6_6") (pintype "passive"))
      (node (ref "RN2") (pin "7") (pinfunction "7_7") (pintype "passive"))
      (node (ref "RN2") (pin "8") (pinfunction "8_8") (pintype "passive"))
      (node (ref "RN3") (pin "5") (pinfunction "5_5") (pintype "passive"))
      (node (ref "RN3") (pin "6") (pinfunction "6_6") (pintype "passive"))
      (node (ref "RN3") (pin "7") (pinfunction "7_7") (pintype "passive"))
      (node (ref "RN3") (pin "8") (pinfunction "8_8") (pintype "passive"))
    )
    (net (code "187") (name "VCC12V") (class "Default")
      (node (ref "CN1") (pin "P$149") (pinfunction "12V_P149_P$149") (pintype "bidirectional"))
    )
    (net (code "188") (name "VCC33") (class "Default")
      (node (ref "C1") (pin "1") (pinfunction "P$1_1") (pintype "passive"))
      (node (ref "C10") (pin "1") (pinfunction "1_1") (pintype "passive"))
      (node (ref "C11") (pin "1") (pinfunction "1_1") (pintype "passive"))
      (node (ref "C19") (pin "1") (pinfunction "1_1") (pintype "passive"))
      (node (ref "C21") (pin "1") (pinfunction "P$1_1") (pintype "passive"))
      (node (ref "C23") (pin "1") (pinfunction "1_1") (pintype "passive"))
      (node (ref "C34") (pin "1") (pinfunction "1_1") (pintype "passive"))
      (node (ref "C38") (pin "1") (pinfunction "1_1") (pintype "passive"))
      (node (ref "C39") (pin "2") (pinfunction "2_2") (pintype "passive"))
      (node (ref "C40") (pin "2") (pinfunction "2_2") (pintype "passive"))
      (node (ref "C41") (pin "2") (pinfunction "2_2") (pintype "passive"))
      (node (ref "C42") (pin "1") (pinfunction "1_1") (pintype "passive"))
      (node (ref "C43") (pin "2") (pinfunction "2_2") (pintype "passive"))
      (node (ref "C44") (pin "2") (pinfunction "2_2") (pintype "passive"))
      (node (ref "C45") (pin "2") (pinfunction "2_2") (pintype "passive"))
      (node (ref "C46") (pin "2") (pinfunction "2_2") (pintype "passive"))
      (node (ref "C47") (pin "2") (pinfunction "2_2") (pintype "passive"))
      (node (ref "C48") (pin "2") (pinfunction "2_2") (pintype "passive"))
      (node (ref "C49") (pin "2") (pinfunction "2_2") (pintype "passive"))
      (node (ref "C5") (pin "1") (pinfunction "1_1") (pintype "passive"))
      (node (ref "C58") (pin "2") (pinfunction "2_2") (pintype "passive"))
      (node (ref "C6") (pin "1") (pinfunction "P$1_1") (pintype "passive"))
      (node (ref "C62") (pin "2") (pinfunction "2_2") (pintype "passive"))
      (node (ref "C63") (pin "2") (pinfunction "2_2") (pintype "passive"))
      (node (ref "C7") (pin "1") (pinfunction "1_1") (pintype "passive"))
      (node (ref "C76") (pin "1") (pinfunction "1_1") (pintype "passive"))
      (node (ref "C8") (pin "1") (pinfunction "P$1_1") (pintype "passive"))
      (node (ref "C81") (pin "2") (pinfunction "2_2") (pintype "passive"))
      (node (ref "C84") (pin "2") (pinfunction "P$2_2") (pintype "passive"))
      (node (ref "C85") (pin "2") (pinfunction "P$2_2") (pintype "passive"))
      (node (ref "C9") (pin "1") (pinfunction "P$1_1") (pintype "passive"))
      (node (ref "IC1") (pin "2") (pinfunction "OUT_2") (pintype "output"))
      (node (ref "IC1") (pin "4") (pinfunction "OUT_4") (pintype "output"))
      (node (ref "IC7") (pin "1") (pinfunction "VDD(1)_1") (pintype "input"))
      (node (ref "IC7") (pin "14") (pinfunction "VDD(2)_14") (pintype "input"))
      (node (ref "IC7") (pin "27") (pinfunction "VDD(3)_27") (pintype "input"))
      (node (ref "IC7") (pin "3") (pinfunction "VDDQ(1)_3") (pintype "input"))
      (node (ref "IC7") (pin "43") (pinfunction "VDDQ(3)_43") (pintype "input"))
      (node (ref "IC7") (pin "49") (pinfunction "VDDQ(4)_49") (pintype "input"))
      (node (ref "IC7") (pin "9") (pinfunction "VDDQ(2)_9") (pintype "input"))
      (node (ref "IC8") (pin "1") (pinfunction "VDD(1)_1") (pintype "input"))
      (node (ref "IC8") (pin "14") (pinfunction "VDD(2)_14") (pintype "input"))
      (node (ref "IC8") (pin "27") (pinfunction "VDD(3)_27") (pintype "input"))
      (node (ref "IC8") (pin "3") (pinfunction "VDDQ(1)_3") (pintype "input"))
      (node (ref "IC8") (pin "43") (pinfunction "VDDQ(3)_43") (pintype "input"))
      (node (ref "IC8") (pin "49") (pinfunction "VDDQ(4)_49") (pintype "input"))
      (node (ref "IC8") (pin "9") (pinfunction "VDDQ(2)_9") (pintype "input"))
      (node (ref "JTAG1") (pin "6") (pinfunction "6_6") (pintype "passive"))
      (node (ref "OSC2") (pin "4") (pinfunction "VCC_4") (pintype "power_in"))
      (node (ref "RAMCPLD") (pin "1") (pinfunction "VCCIO(1)_1") (pintype "input"))
      (node (ref "RAMCPLD") (pin "109") (pinfunction "VCCIO(5)_109") (pintype "input"))
      (node (ref "RAMCPLD") (pin "127") (pinfunction "VCCIO(6)_127") (pintype "input"))
      (node (ref "RAMCPLD") (pin "141") (pinfunction "VCCINT(4)_141") (pintype "input"))
      (node (ref "RAMCPLD") (pin "37") (pinfunction "VCCIO(2)_37") (pintype "input"))
      (node (ref "RAMCPLD") (pin "42") (pinfunction "VCCINT(2)_42") (pintype "input"))
      (node (ref "RAMCPLD") (pin "55") (pinfunction "VCCIO(3)_55") (pintype "input"))
      (node (ref "RAMCPLD") (pin "73") (pinfunction "VCCIO(4)_73") (pintype "input"))
      (node (ref "RAMCPLD") (pin "8") (pinfunction "VCCINT(1)_8") (pintype "input"))
      (node (ref "RAMCPLD") (pin "84") (pinfunction "VCCINT(3)_84") (pintype "input"))
      (node (ref "U1") (pin "20") (pinfunction "VCC_20") (pintype "power_in"))
      (node (ref "U2") (pin "20") (pinfunction "VCC_20") (pintype "power_in"))
      (node (ref "U3") (pin "20") (pinfunction "VCC_20") (pintype "power_in"))
      (node (ref "U4") (pin "20") (pinfunction "VCC_20") (pintype "power_in"))
    )
    (net (code "189") (name "unconnected-(CN1--12V_P150-PadP$150)") (class "Default")
      (node (ref "CN1") (pin "P$150") (pinfunction "-12V_P150_P$150") (pintype "bidirectional"))
    )
    (net (code "190") (name "unconnected-(CN1-AGND_P146-PadP$146)") (class "Default")
      (node (ref "CN1") (pin "P$146") (pinfunction "AGND_P146_P$146") (pintype "bidirectional"))
    )
    (net (code "191") (name "unconnected-(CN1-CCK_P117-PadP$117)") (class "Default")
      (node (ref "CN1") (pin "P$117") (pinfunction "CCK_P117_P$117") (pintype "bidirectional"))
    )
    (net (code "192") (name "unconnected-(CN1-GND_P119-PadP$119)") (class "Default")
      (node (ref "CN1") (pin "P$119") (pinfunction "GND_P119_P$119") (pintype "bidirectional"))
    )
    (net (code "193") (name "unconnected-(CN1-GND_P139-PadP$139)") (class "Default")
      (node (ref "CN1") (pin "P$139") (pinfunction "GND_P139_P$139") (pintype "bidirectional"))
    )
    (net (code "194") (name "unconnected-(CN1-LEFT_P147-PadP$147)") (class "Default")
      (node (ref "CN1") (pin "P$147") (pinfunction "LEFT_P147_P$147") (pintype "bidirectional"))
    )
    (net (code "195") (name "unconnected-(CN1-RIGHT_P148-PadP$148)") (class "Default")
      (node (ref "CN1") (pin "P$148") (pinfunction "RIGHT_P148_P$148") (pintype "bidirectional"))
    )
    (net (code "196") (name "unconnected-(CN1-SYSTEM0_P142-PadP$142)") (class "Default")
      (node (ref "CN1") (pin "P$142") (pinfunction "SYSTEM0_P142_P$142") (pintype "bidirectional"))
    )
    (net (code "197") (name "unconnected-(CN1-SYSTEM1_P141-PadP$141)") (class "Default")
      (node (ref "CN1") (pin "P$141") (pinfunction "SYSTEM1_P141_P$141") (pintype "bidirectional"))
    )
    (net (code "198") (name "unconnected-(CN1-VCC_P140-PadP$140)") (class "Default")
      (node (ref "CN1") (pin "P$140") (pinfunction "VCC_P140_P$140") (pintype "bidirectional"))
    )
    (net (code "199") (name "unconnected-(CN1-XRDY_P134-PadP$134)") (class "Default")
      (node (ref "CN1") (pin "P$134") (pinfunction "XRDY_P134_P$134") (pintype "bidirectional"))
    )
    (net (code "200") (name "unconnected-(CN1-~{BGACK}(NC)_P113-PadP$113)") (class "Default")
      (node (ref "CN1") (pin "P$113") (pinfunction "~{BGACK}(NC)_P113_P$113") (pintype "bidirectional"))
    )
    (net (code "201") (name "unconnected-(CN1-~{CBACK}(NC)_P110-PadP$110)") (class "Default")
      (node (ref "CN1") (pin "P$110") (pinfunction "~{CBACK}(NC)_P110_P$110") (pintype "bidirectional"))
    )
    (net (code "202") (name "unconnected-(CN1-~{CBREQ}(NC)_109-PadP$109)") (class "Default")
      (node (ref "CN1") (pin "P$109") (pinfunction "~{CBREQ}(NC)_109_P$109") (pintype "bidirectional"))
    )
    (net (code "203") (name "unconnected-(CN1-~{CC_ENA}_P126-PadP$126)") (class "Default")
      (node (ref "CN1") (pin "P$126") (pinfunction "~{CC_ENA}_P126_P$126") (pintype "bidirectional"))
    )
    (net (code "204") (name "unconnected-(CN1-~{CIIN}(NC)_P107-PadP$107)") (class "Default")
      (node (ref "CN1") (pin "P$107") (pinfunction "~{CIIN}(NC)_P107_P$107") (pintype "bidirectional"))
    )
    (net (code "205") (name "unconnected-(CN1-~{CIOUT}(NC)_P108-PadP$108)") (class "Default")
      (node (ref "CN1") (pin "P$108") (pinfunction "~{CIOUT}(NC)_P108_P$108") (pintype "bidirectional"))
    )
    (net (code "206") (name "unconnected-(CN1-~{ECS}(NC)_P87-PadP$87)") (class "Default")
      (node (ref "CN1") (pin "P$87") (pinfunction "~{ECS}(NC)_P87_P$87") (pintype "bidirectional"))
    )
    (net (code "207") (name "unconnected-(CN1-~{FLASH}_P124-PadP$124)") (class "Default")
      (node (ref "CN1") (pin "P$124") (pinfunction "~{FLASH}_P124_P$124") (pintype "bidirectional"))
    )
    (net (code "208") (name "unconnected-(CN1-~{FPU_CS}_P115-PadP$115)") (class "Default")
      (node (ref "CN1") (pin "P$115") (pinfunction "~{FPU_CS}_P115_P$115") (pintype "bidirectional"))
    )
    (net (code "209") (name "unconnected-(CN1-~{FPU_SENSE}_P116-PadP$116)") (class "Default")
      (node (ref "CN1") (pin "P$116") (pinfunction "~{FPU_SENSE}_P116_P$116") (pintype "bidirectional"))
    )
    (net (code "210") (name "unconnected-(CN1-~{HLT}_P86-PadP$86)") (class "Default")
      (node (ref "CN1") (pin "P$86") (pinfunction "~{HLT}_P86_P$86") (pintype "bidirectional"))
    )
    (net (code "211") (name "unconnected-(CN1-~{IORDY}_P129-PadP$129)") (class "Default")
      (node (ref "CN1") (pin "P$129") (pinfunction "~{IORDY}_P129_P$129") (pintype "bidirectional"))
    )
    (net (code "212") (name "unconnected-(CN1-~{IOWR}_P130-PadP$130)") (class "Default")
      (node (ref "CN1") (pin "P$130") (pinfunction "~{IOWR}_P130_P$130") (pintype "bidirectional"))
    )
    (net (code "213") (name "unconnected-(CN1-~{IPEND}(NC)_P84-PadP$84)") (class "Default")
      (node (ref "CN1") (pin "P$84") (pinfunction "~{IPEND}(NC)_P84_P$84") (pintype "bidirectional"))
    )
    (net (code "214") (name "unconnected-(CN1-~{KB_RESET}_P128-PadP$128)") (class "Default")
      (node (ref "CN1") (pin "P$128") (pinfunction "~{KB_RESET}_P128_P$128") (pintype "bidirectional"))
    )
    (net (code "215") (name "unconnected-(CN1-~{NET_CS}_P121-PadP$121)") (class "Default")
      (node (ref "CN1") (pin "P$121") (pinfunction "~{NET_CS}_P121_P$121") (pintype "bidirectional"))
    )
    (net (code "216") (name "unconnected-(CN1-~{OCS}(NC)_P88-PadP$88)") (class "Default")
      (node (ref "CN1") (pin "P$88") (pinfunction "~{OCS}(NC)_P88_P$88") (pintype "bidirectional"))
    )
    (net (code "217") (name "unconnected-(CN1-~{OE}_P131-PadP$131)") (class "Default")
      (node (ref "CN1") (pin "P$131") (pinfunction "~{OE}_P131_P$131") (pintype "bidirectional"))
    )
    (net (code "218") (name "unconnected-(CN1-~{REG}_P125-PadP$125)") (class "Default")
      (node (ref "CN1") (pin "P$125") (pinfunction "~{REG}_P125_P$125") (pintype "bidirectional"))
    )
    (net (code "219") (name "unconnected-(CN1-~{RMC}_P106-PadP$106)") (class "Default")
      (node (ref "CN1") (pin "P$106") (pinfunction "~{RMC}_P106_P$106") (pintype "bidirectional"))
    )
    (net (code "220") (name "unconnected-(CN1-~{RTC_CS}_P123-PadP$123)") (class "Default")
      (node (ref "CN1") (pin "P$123") (pinfunction "~{RTC_CS}_P123_P$123") (pintype "bidirectional"))
    )
    (net (code "221") (name "unconnected-(CN1-~{SPARE_CS}_P122-PadP$122)") (class "Default")
      (node (ref "CN1") (pin "P$122") (pinfunction "~{SPARE_CS}_P122_P$122") (pintype "bidirectional"))
    )
    (net (code "222") (name "unconnected-(CN1-~{STERM}(NC)_P95-PadP$95)") (class "Default")
      (node (ref "CN1") (pin "P$95") (pinfunction "~{STERM}(NC)_P95_P$95") (pintype "bidirectional"))
    )
    (net (code "223") (name "unconnected-(CN1-~{WAIT}_P127-PadP$127)") (class "Default")
      (node (ref "CN1") (pin "P$127") (pinfunction "~{WAIT}_P127_P$127") (pintype "bidirectional"))
    )
    (net (code "224") (name "unconnected-(CN1-~{WE}_P132-PadP$132)") (class "Default")
      (node (ref "CN1") (pin "P$132") (pinfunction "~{WE}_P132_P$132") (pintype "bidirectional"))
    )
    (net (code "225") (name "unconnected-(CN1-~{WIDE}_P136-PadP$136)") (class "Default")
      (node (ref "CN1") (pin "P$136") (pinfunction "~{WIDE}_P136_P$136") (pintype "bidirectional"))
    )
    (net (code "226") (name "unconnected-(CN1-~{ZORRO}_P135-PadP$135)") (class "Default")
      (node (ref "CN1") (pin "P$135") (pinfunction "~{ZORRO}_P135_P$135") (pintype "bidirectional"))
    )
    (net (code "227") (name "unconnected-(IC2A-ECS-PadM02)") (class "Default")
      (node (ref "IC2") (pin "M02") (pinfunction "ECS_M02") (pintype "output"))
    )
    (net (code "228") (name "unconnected-(IC2A-IPEND-PadE13)") (class "Default")
      (node (ref "IC2") (pin "E13") (pinfunction "IPEND_E13") (pintype "output"))
    )
    (net (code "229") (name "unconnected-(IC2A-OCS-PadD03)") (class "Default")
      (node (ref "IC2") (pin "D03") (pinfunction "OCS_D03") (pintype "output"))
    )
    (net (code "230") (name "unconnected-(IC2A-RMC-PadB01)") (class "Default")
      (node (ref "IC2") (pin "B01") (pinfunction "RMC_B01") (pintype "output"))
    )
    (net (code "231") (name "unconnected-(IC7-NC-Pad40)") (class "Default")
      (node (ref "IC7") (pin "40") (pinfunction "NC_40") (pintype "input"))
    )
    (net (code "232") (name "unconnected-(IC8-NC-Pad40)") (class "Default")
      (node (ref "IC8") (pin "40") (pinfunction "NC_40") (pintype "input"))
    )
    (net (code "233") (name "unconnected-(IDEAB-S-Pad34)") (class "Default")
      (node (ref "IDE") (pin "34") (pinfunction "S_34") (pintype "passive"))
    )
    (net (code "234") (name "unconnected-(IDEAG-S-Pad39)") (class "Default")
      (node (ref "IDE") (pin "39") (pinfunction "S_39") (pintype "passive"))
    )
    (net (code "235") (name "unconnected-(IDEM-S-Pad20)") (class "Default")
      (node (ref "IDE") (pin "20") (pinfunction "S_20") (pintype "passive"))
    )
    (net (code "236") (name "unconnected-(IDEN-S-Pad21)") (class "Default")
      (node (ref "IDE") (pin "21") (pinfunction "S_21") (pintype "passive"))
    )
    (net (code "237") (name "unconnected-(IDEU-S-Pad28)") (class "Default")
      (node (ref "IDE") (pin "28") (pinfunction "S_28") (pintype "passive"))
    )
    (net (code "238") (name "unconnected-(IDEV-S-Pad29)") (class "Default")
      (node (ref "IDE") (pin "29") (pinfunction "S_29") (pintype "passive"))
    )
    (net (code "239") (name "unconnected-(IDEZ-S-Pad32)") (class "Default")
      (node (ref "IDE") (pin "32") (pinfunction "S_32") (pintype "passive"))
    )
    (net (code "240") (name "unconnected-(OSC2-INH-Pad1)") (class "Default")
      (node (ref "OSC2") (pin "1") (pinfunction "INH_1") (pintype "bidirectional"))
    )
    (net (code "241") (name "unconnected-(RAMCPLD-PB1{slash}16-Pad35)") (class "Default")
      (node (ref "RAMCPLD") (pin "35") (pinfunction "PB1/16_35") (pintype "input"))
    )
    (net (code "242") (name "unconnected-(RAMCPLD-PB1{slash}17{slash}GCK1-Pad30)") (class "Default")
      (node (ref "RAMCPLD") (pin "30") (pinfunction "PB1/17/GCK1_30") (pintype "input"))
    )
    (net (code "243") (name "unconnected-(RAMCPLD-PB3{slash}1-Pad39)") (class "Default")
      (node (ref "RAMCPLD") (pin "39") (pinfunction "PB3/1_39") (pintype "input"))
    )
    (net (code "244") (name "unconnected-(RAMCPLD-PB3{slash}3-Pad41)") (class "Default")
      (node (ref "RAMCPLD") (pin "41") (pinfunction "PB3/3_41") (pintype "input"))
    )
    (net (code "245") (name "unconnected-(RAMCPLD-PB3{slash}8{slash}GCK3-Pad38)") (class "Default")
      (node (ref "RAMCPLD") (pin "38") (pinfunction "PB3/8/GCK3_38") (pintype "input"))
    )
    (net (code "246") (name "unconnected-(RAMCPLD-PB3{slash}9-Pad40)") (class "Default")
      (node (ref "RAMCPLD") (pin "40") (pinfunction "PB3/9_40") (pintype "input"))
    )
    (net (code "247") (name "unconnected-(RAMCPLD-PB4{slash}8-Pad130)") (class "Default")
      (node (ref "RAMCPLD") (pin "130") (pinfunction "PB4/8_130") (pintype "input"))
    )
    (net (code "248") (name "unconnected-(RAMCPLD-PB4{slash}9-Pad131)") (class "Default")
      (node (ref "RAMCPLD") (pin "131") (pinfunction "PB4/9_131") (pintype "input"))
    )
    (net (code "249") (name "unconnected-(RAMCPLD-PB4{slash}13-Pad137)") (class "Default")
      (node (ref "RAMCPLD") (pin "137") (pinfunction "PB4/13_137") (pintype "input"))
    )
    (net (code "250") (name "unconnected-(RN2-Pad2)") (class "Default")
      (node (ref "RN2") (pin "2") (pinfunction "2_2") (pintype "passive"))
    )
    (net (code "251") (name "unconnected-(RN2-Pad3)") (class "Default")
      (node (ref "RN2") (pin "3") (pinfunction "3_3") (pintype "passive"))
    )
    (net (code "252") (name "unconnected-(U1-NC-Pad1)") (class "Default")
      (node (ref "U1") (pin "1") (pinfunction "NC_1") (pintype "no_connect"))
    )
    (net (code "253") (name "unconnected-(U2-NC-Pad1)") (class "Default")
      (node (ref "U2") (pin "1") (pinfunction "NC_1") (pintype "no_connect"))
    )
    (net (code "254") (name "unconnected-(U3-NC-Pad1)") (class "Default")
      (node (ref "U3") (pin "1") (pinfunction "NC_1") (pintype "no_connect"))
    )
    (net (code "255") (name "unconnected-(U4-NC-Pad1)") (class "Default")
      (node (ref "U4") (pin "1") (pinfunction "NC_1") (pintype "no_connect"))
    )
  )
)
